# flight_sim_sch.net
KiCad netlist of a schematic drawn in EAGLE
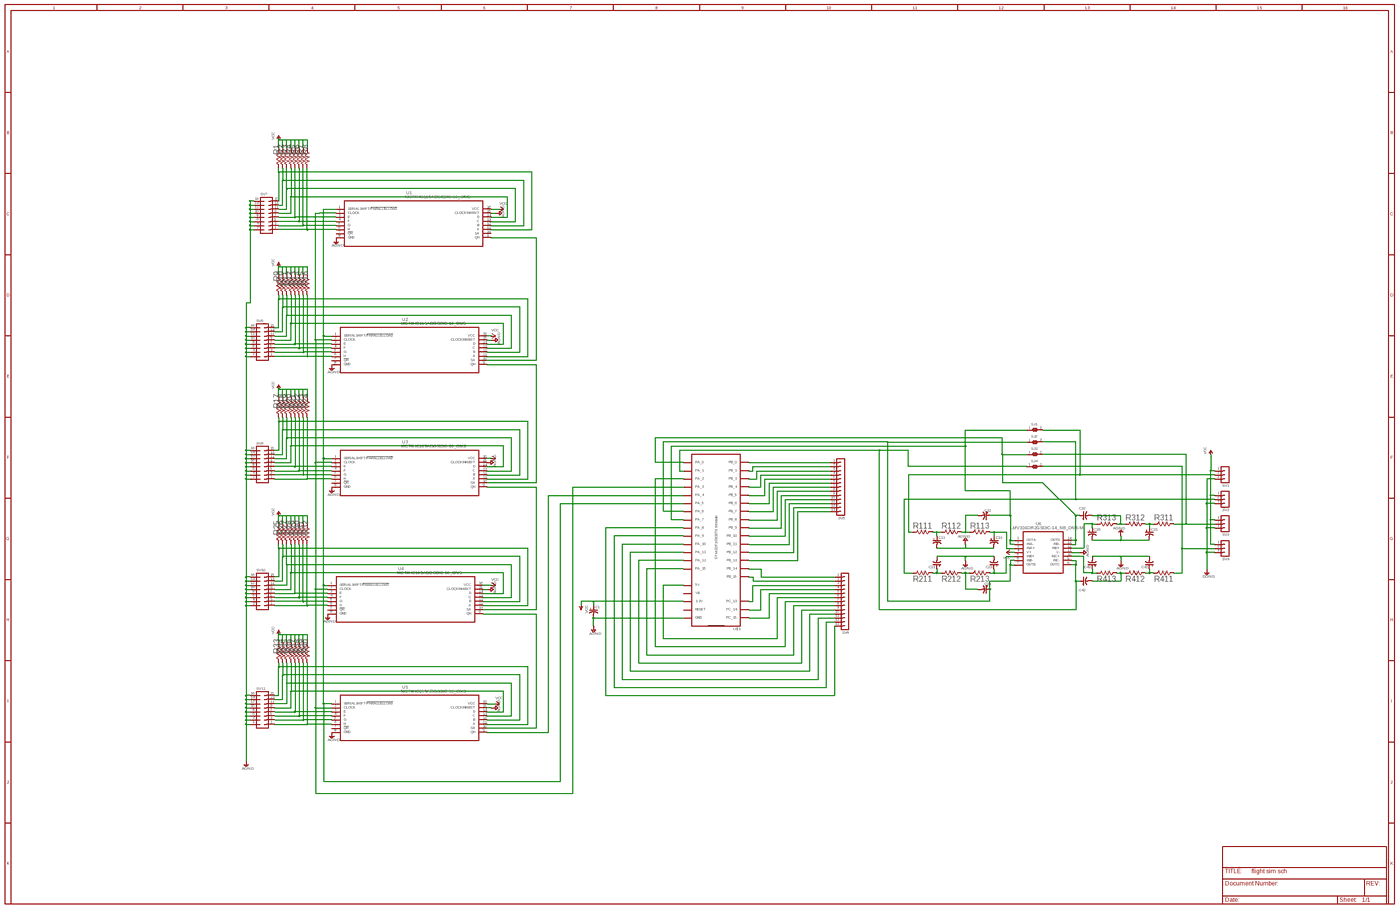
[diagram p0: schematic, sheet 1, overview]
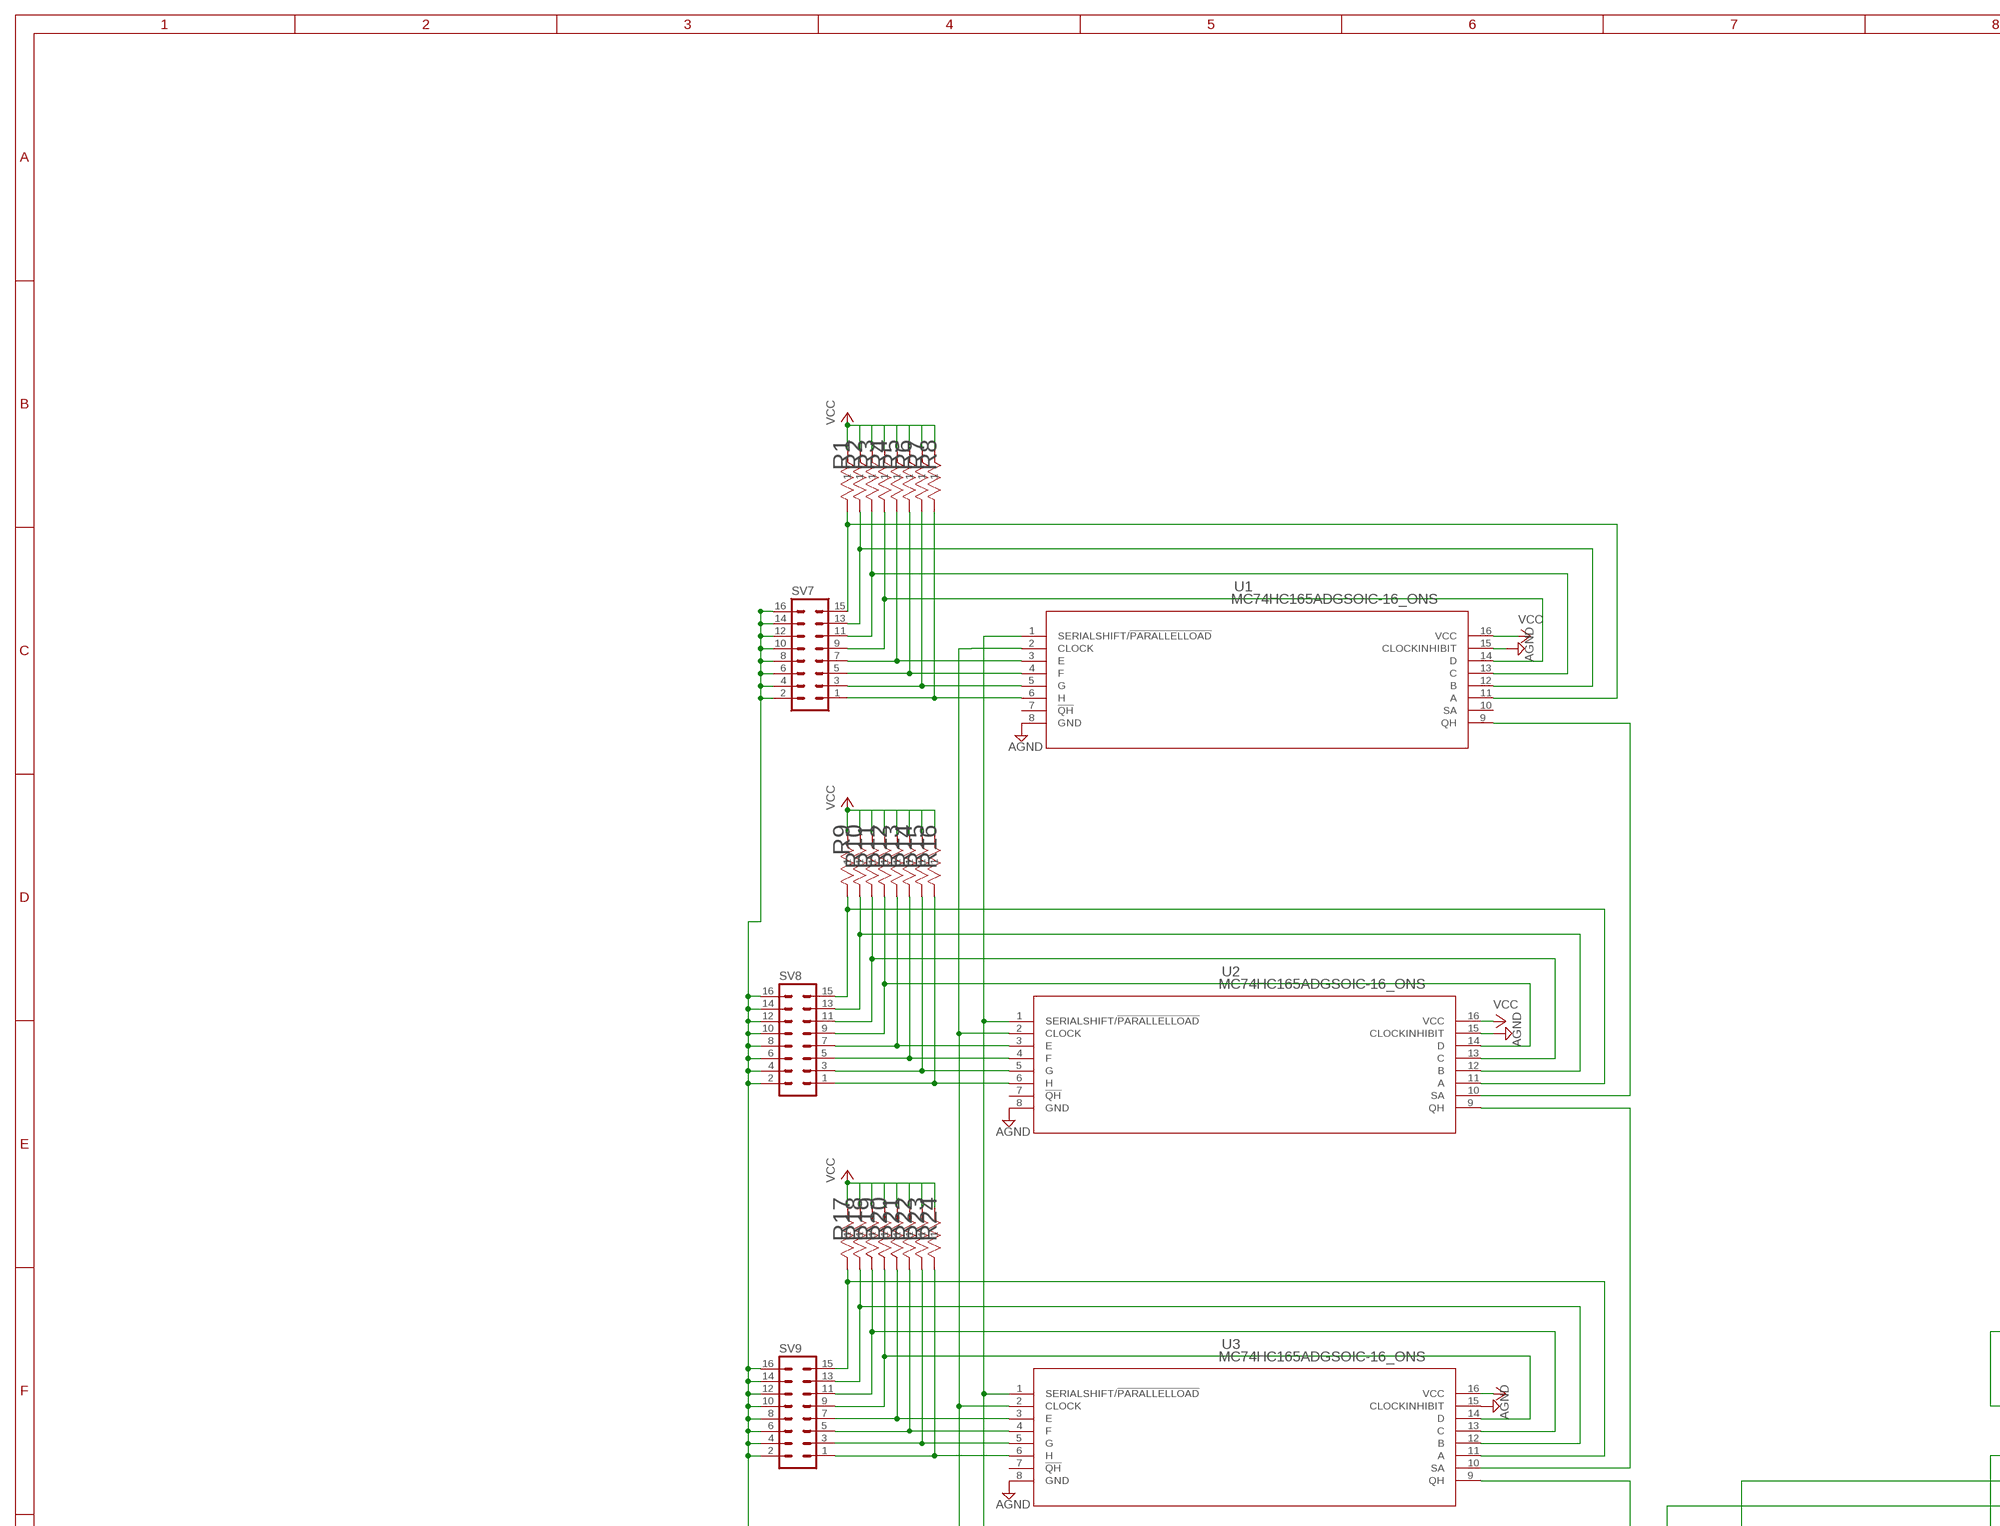
[diagram p1: schematic, sheet 1, part 1 of 4]
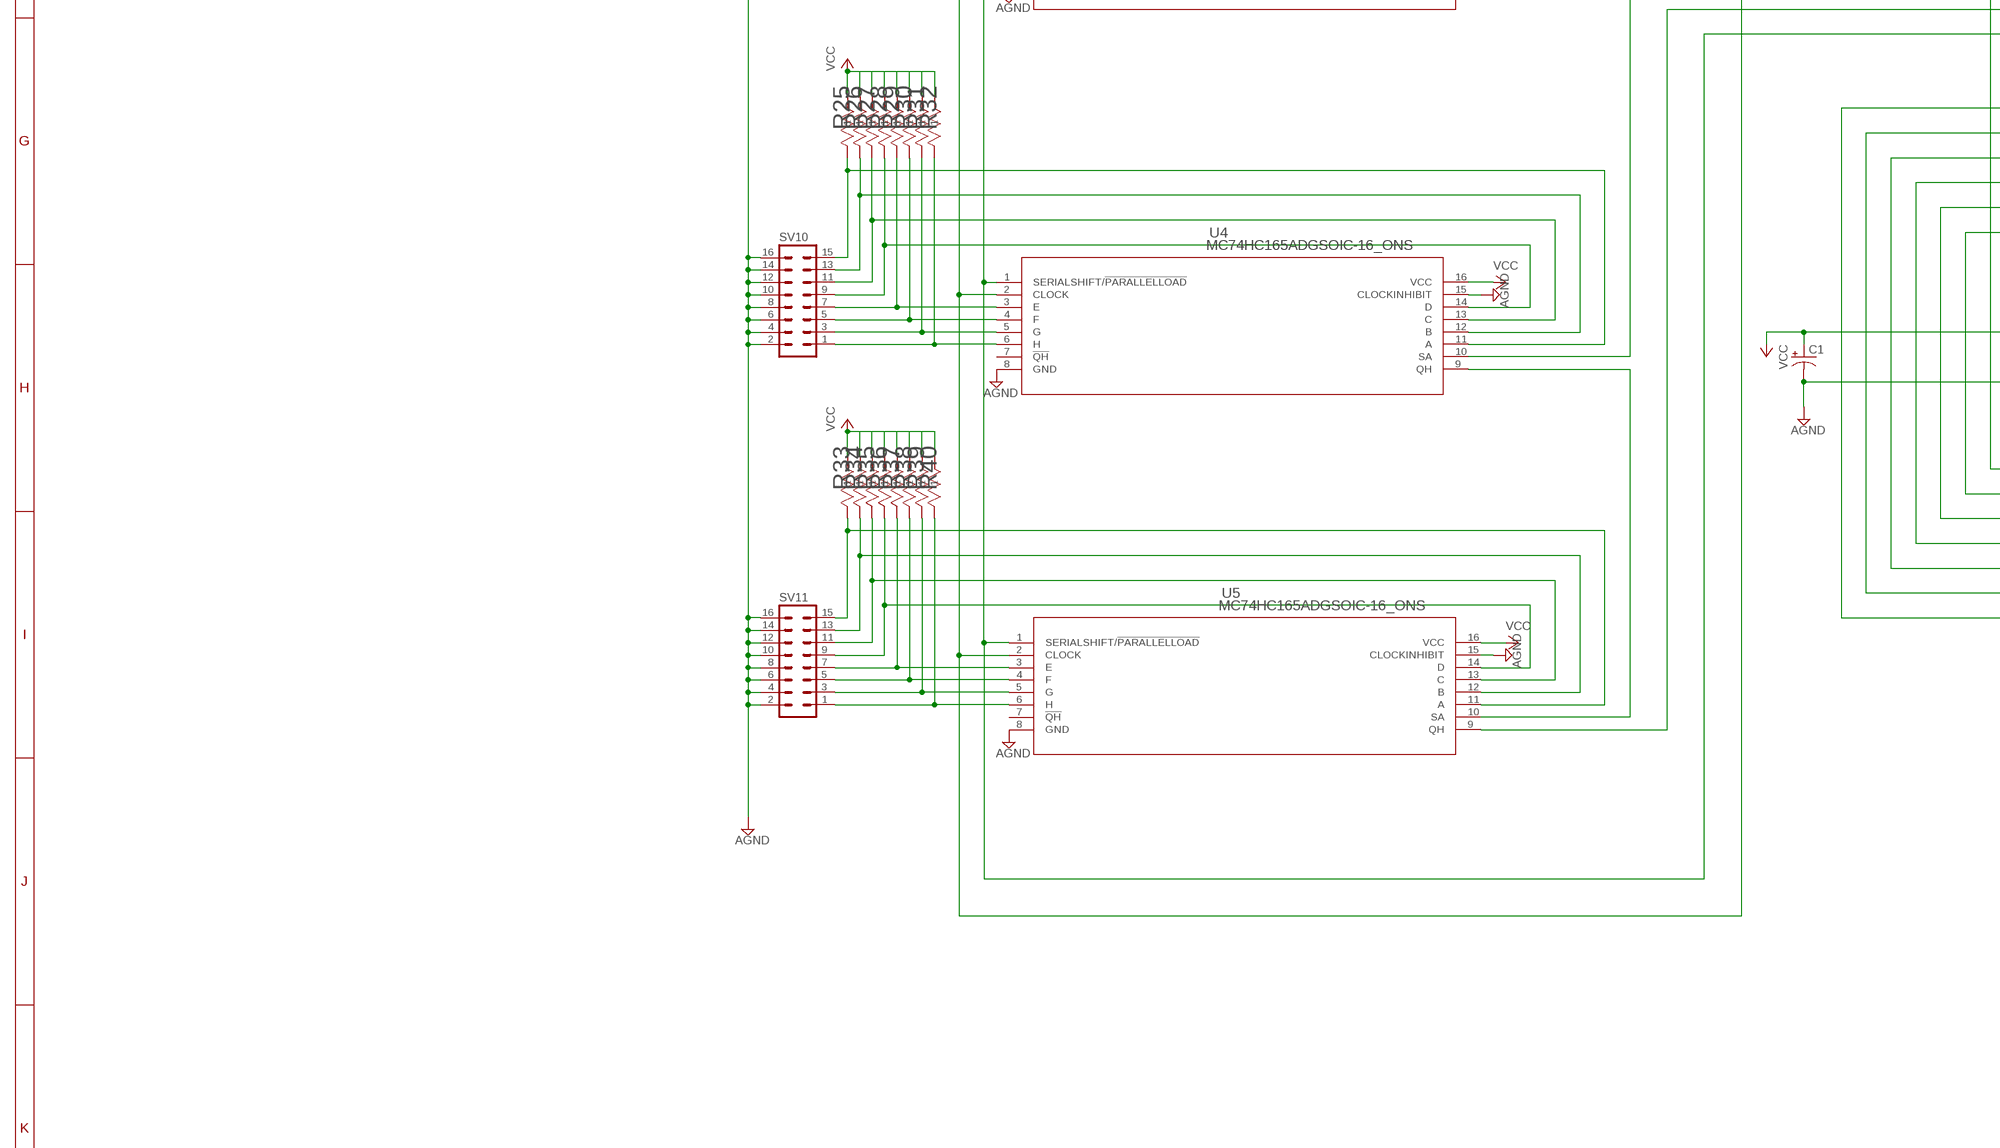
[diagram p2: schematic, sheet 1, part 2 of 4]
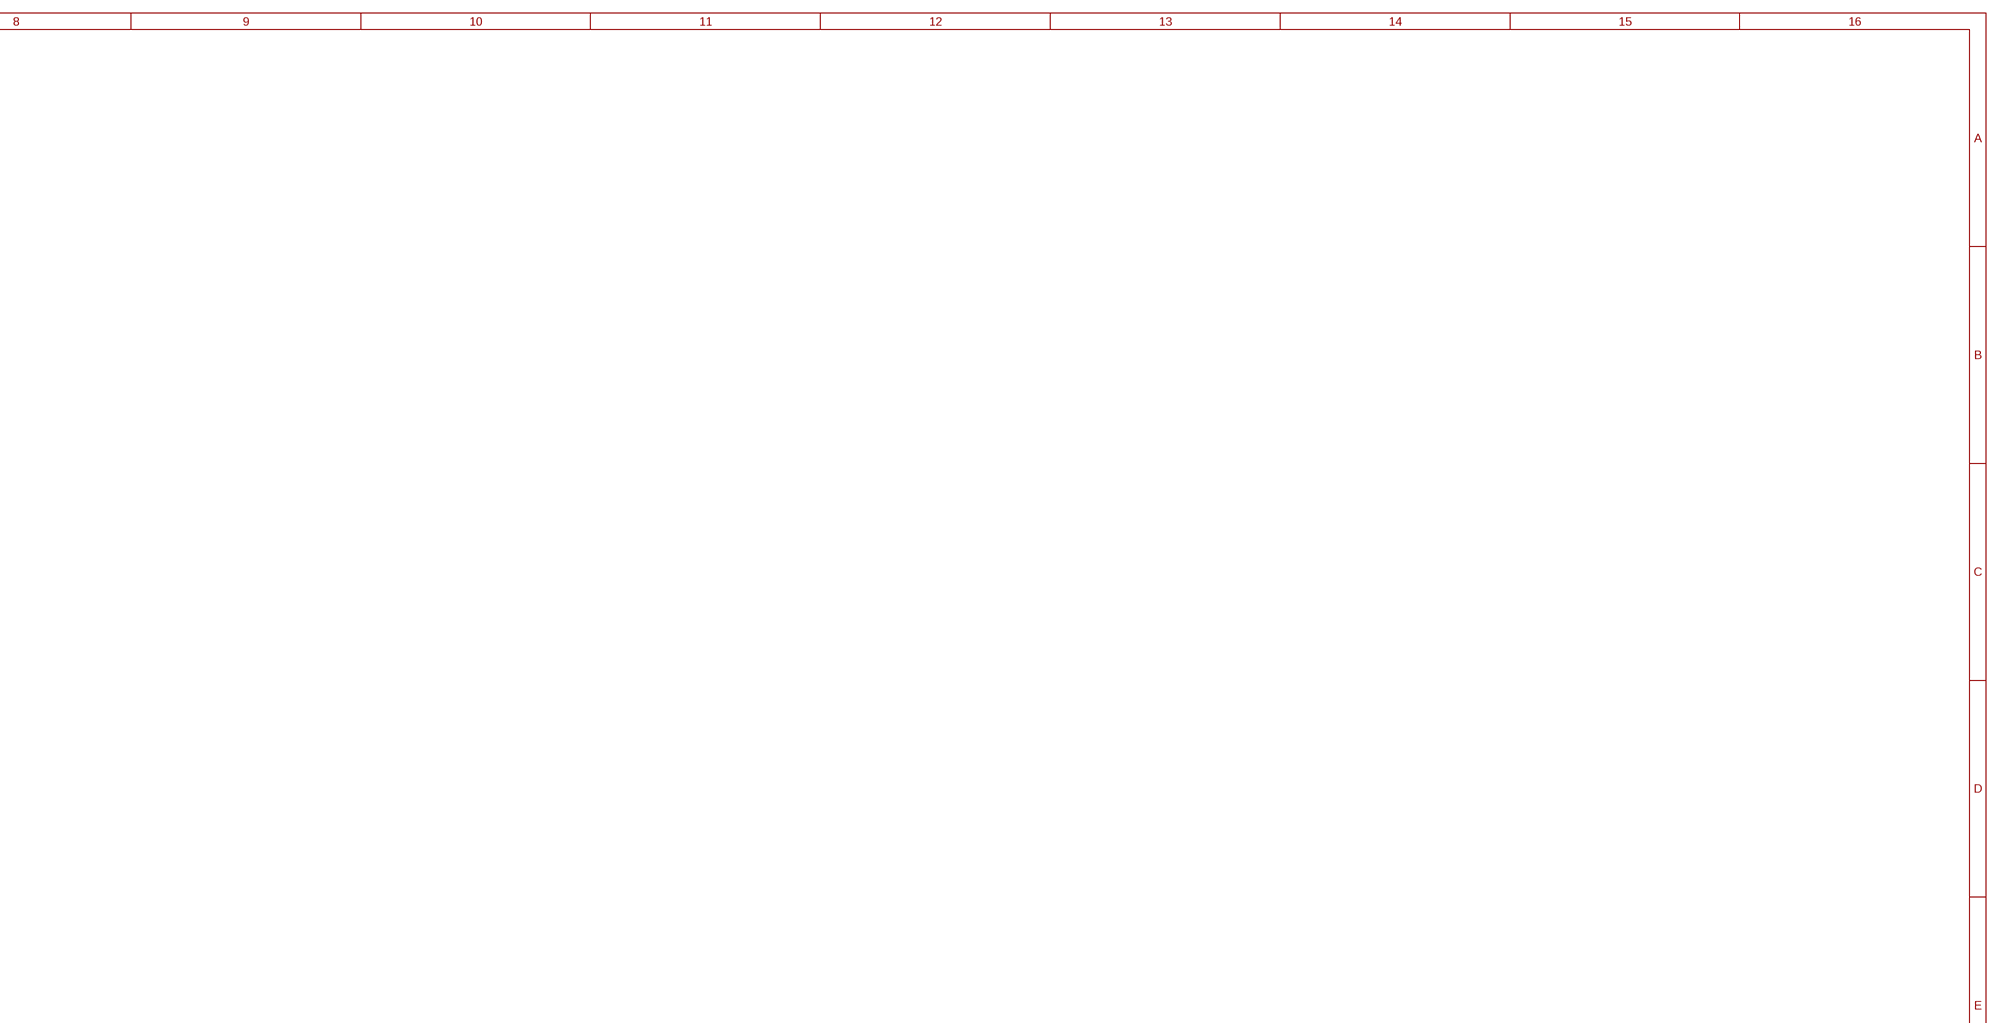
[diagram p3: schematic, sheet 1, part 3 of 4]
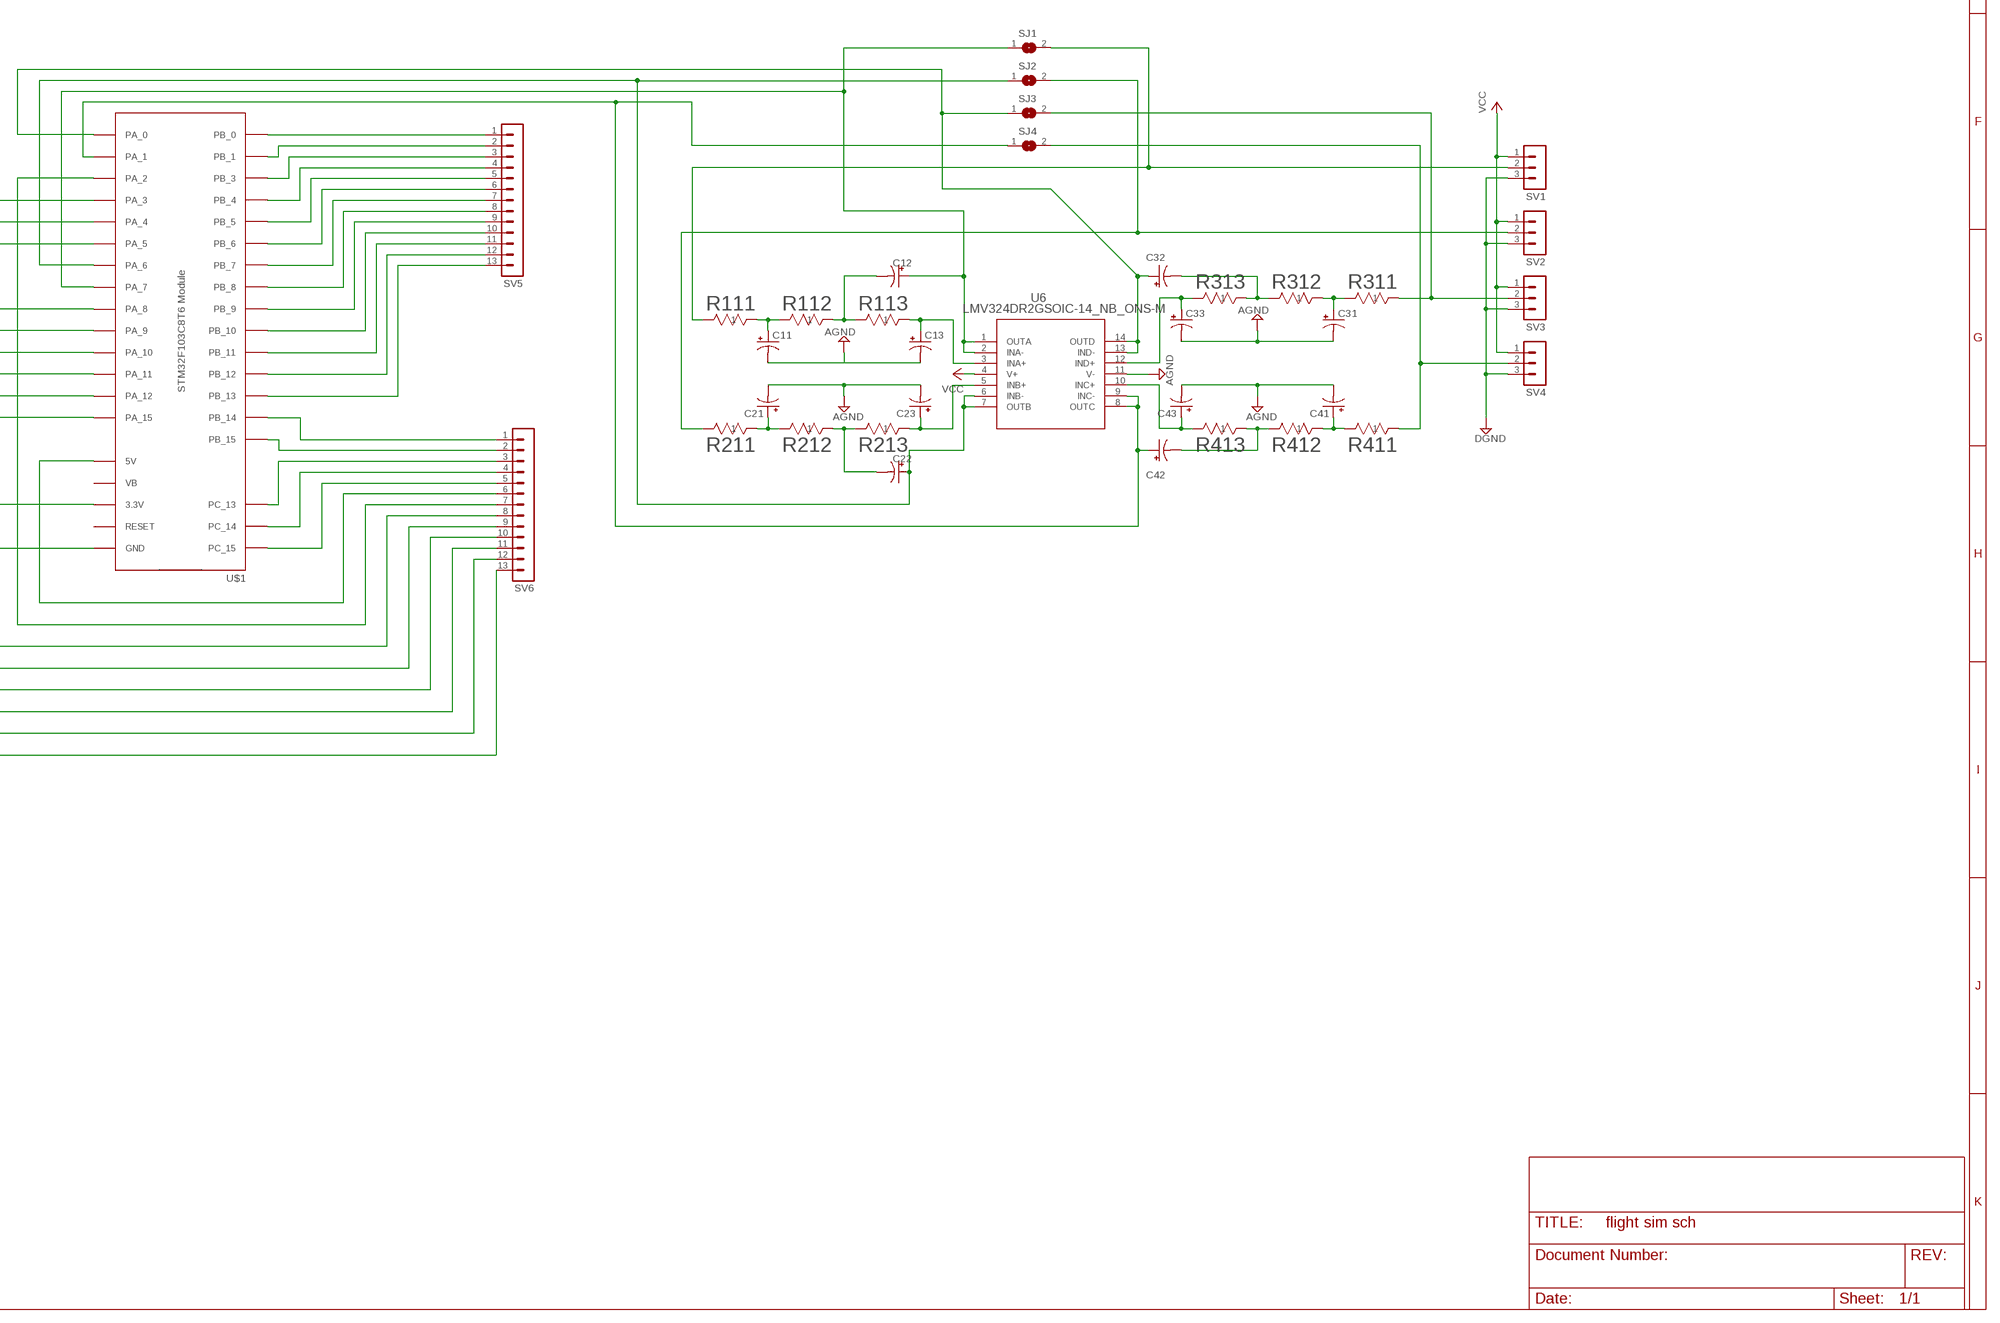
[diagram p4: schematic, sheet 1, part 4 of 4]

(export (version "E")
  (design (tool "Eeschema 10.0.6"))
  (components
    (comp (ref "C1")
      (value "CPOL-USE1.8-4")
      (footprint "eagle-import:E1,8-4")
      (libsource (lib "eagle-import") (part "CPOL-USE1.8-4"))
    )
    (comp (ref "C11")
      (value "CPOL-USE1.8-4")
      (footprint "eagle-import:E1,8-4")
      (libsource (lib "eagle-import") (part "CPOL-USE1.8-4"))
    )
    (comp (ref "C12")
      (value "CPOL-USE1.8-4")
      (footprint "eagle-import:E1,8-4")
      (libsource (lib "eagle-import") (part "CPOL-USE1.8-4"))
    )
    (comp (ref "C13")
      (value "CPOL-USE1.8-4")
      (footprint "eagle-import:E1,8-4")
      (libsource (lib "eagle-import") (part "CPOL-USE1.8-4"))
    )
    (comp (ref "C21")
      (value "CPOL-USE1.8-4")
      (footprint "eagle-import:E1,8-4")
      (libsource (lib "eagle-import") (part "CPOL-USE1.8-4"))
    )
    (comp (ref "C22")
      (value "CPOL-USE1.8-4")
      (footprint "eagle-import:E1,8-4")
      (libsource (lib "eagle-import") (part "CPOL-USE1.8-4"))
    )
    (comp (ref "C23")
      (value "CPOL-USE1.8-4")
      (footprint "eagle-import:E1,8-4")
      (libsource (lib "eagle-import") (part "CPOL-USE1.8-4"))
    )
    (comp (ref "C31")
      (value "CPOL-USE1.8-4")
      (footprint "eagle-import:E1,8-4")
      (libsource (lib "eagle-import") (part "CPOL-USE1.8-4"))
    )
    (comp (ref "C32")
      (value "CPOL-USE1.8-4")
      (footprint "eagle-import:E1,8-4")
      (libsource (lib "eagle-import") (part "CPOL-USE1.8-4"))
    )
    (comp (ref "C33")
      (value "CPOL-USE1.8-4")
      (footprint "eagle-import:E1,8-4")
      (libsource (lib "eagle-import") (part "CPOL-USE1.8-4"))
    )
    (comp (ref "C41")
      (value "CPOL-USE1.8-4")
      (footprint "eagle-import:E1,8-4")
      (libsource (lib "eagle-import") (part "CPOL-USE1.8-4"))
    )
    (comp (ref "C42")
      (value "CPOL-USE1.8-4")
      (footprint "eagle-import:E1,8-4")
      (libsource (lib "eagle-import") (part "CPOL-USE1.8-4"))
    )
    (comp (ref "C43")
      (value "CPOL-USE1.8-4")
      (footprint "eagle-import:E1,8-4")
      (libsource (lib "eagle-import") (part "CPOL-USE1.8-4"))
    )
    (comp (ref "R1")
      (value "MFR-25FRF52-10KYAG_MF25_YAG")
      (footprint "eagle-import:YAG_MF25_YAG")
      (fields
        (field (name "MANUFACTURER_PART_NUMBER") "MFR-25FRF52-10K")
        (field (name "COPYRIGHT") "Copyright (C) 2022 Ultra Librarian. All rights reserved.")
      )
      (libsource (lib "eagle-import") (part "MFR-25FRF52-10KYAG_MF25_YAG"))
    )
    (comp (ref "R2")
      (value "MFR-25FRF52-10KYAG_MF25_YAG")
      (footprint "eagle-import:YAG_MF25_YAG")
      (fields
        (field (name "MANUFACTURER_PART_NUMBER") "MFR-25FRF52-10K")
        (field (name "COPYRIGHT") "Copyright (C) 2022 Ultra Librarian. All rights reserved.")
      )
      (libsource (lib "eagle-import") (part "MFR-25FRF52-10KYAG_MF25_YAG"))
    )
    (comp (ref "R3")
      (value "MFR-25FRF52-10KYAG_MF25_YAG")
      (footprint "eagle-import:YAG_MF25_YAG")
      (fields
        (field (name "MANUFACTURER_PART_NUMBER") "MFR-25FRF52-10K")
        (field (name "COPYRIGHT") "Copyright (C) 2022 Ultra Librarian. All rights reserved.")
      )
      (libsource (lib "eagle-import") (part "MFR-25FRF52-10KYAG_MF25_YAG"))
    )
    (comp (ref "R4")
      (value "MFR-25FRF52-10KYAG_MF25_YAG")
      (footprint "eagle-import:YAG_MF25_YAG")
      (fields
        (field (name "MANUFACTURER_PART_NUMBER") "MFR-25FRF52-10K")
        (field (name "COPYRIGHT") "Copyright (C) 2022 Ultra Librarian. All rights reserved.")
      )
      (libsource (lib "eagle-import") (part "MFR-25FRF52-10KYAG_MF25_YAG"))
    )
    (comp (ref "R5")
      (value "MFR-25FRF52-10KYAG_MF25_YAG")
      (footprint "eagle-import:YAG_MF25_YAG")
      (fields
        (field (name "MANUFACTURER_PART_NUMBER") "MFR-25FRF52-10K")
        (field (name "COPYRIGHT") "Copyright (C) 2022 Ultra Librarian. All rights reserved.")
      )
      (libsource (lib "eagle-import") (part "MFR-25FRF52-10KYAG_MF25_YAG"))
    )
    (comp (ref "R6")
      (value "MFR-25FRF52-10KYAG_MF25_YAG")
      (footprint "eagle-import:YAG_MF25_YAG")
      (fields
        (field (name "MANUFACTURER_PART_NUMBER") "MFR-25FRF52-10K")
        (field (name "COPYRIGHT") "Copyright (C) 2022 Ultra Librarian. All rights reserved.")
      )
      (libsource (lib "eagle-import") (part "MFR-25FRF52-10KYAG_MF25_YAG"))
    )
    (comp (ref "R7")
      (value "MFR-25FRF52-10KYAG_MF25_YAG")
      (footprint "eagle-import:YAG_MF25_YAG")
      (fields
        (field (name "MANUFACTURER_PART_NUMBER") "MFR-25FRF52-10K")
        (field (name "COPYRIGHT") "Copyright (C) 2022 Ultra Librarian. All rights reserved.")
      )
      (libsource (lib "eagle-import") (part "MFR-25FRF52-10KYAG_MF25_YAG"))
    )
    (comp (ref "R8")
      (value "MFR-25FRF52-10KYAG_MF25_YAG")
      (footprint "eagle-import:YAG_MF25_YAG")
      (fields
        (field (name "MANUFACTURER_PART_NUMBER") "MFR-25FRF52-10K")
        (field (name "COPYRIGHT") "Copyright (C) 2022 Ultra Librarian. All rights reserved.")
      )
      (libsource (lib "eagle-import") (part "MFR-25FRF52-10KYAG_MF25_YAG"))
    )
    (comp (ref "R9")
      (value "MFR-25FRF52-10KYAG_MF25_YAG")
      (footprint "eagle-import:YAG_MF25_YAG")
      (fields
        (field (name "MANUFACTURER_PART_NUMBER") "MFR-25FRF52-10K")
        (field (name "COPYRIGHT") "Copyright (C) 2022 Ultra Librarian. All rights reserved.")
      )
      (libsource (lib "eagle-import") (part "MFR-25FRF52-10KYAG_MF25_YAG"))
    )
    (comp (ref "R10")
      (value "MFR-25FRF52-10KYAG_MF25_YAG")
      (footprint "eagle-import:YAG_MF25_YAG")
      (fields
        (field (name "MANUFACTURER_PART_NUMBER") "MFR-25FRF52-10K")
        (field (name "COPYRIGHT") "Copyright (C) 2022 Ultra Librarian. All rights reserved.")
      )
      (libsource (lib "eagle-import") (part "MFR-25FRF52-10KYAG_MF25_YAG"))
    )
    (comp (ref "R11")
      (value "MFR-25FRF52-10KYAG_MF25_YAG")
      (footprint "eagle-import:YAG_MF25_YAG")
      (fields
        (field (name "MANUFACTURER_PART_NUMBER") "MFR-25FRF52-10K")
        (field (name "COPYRIGHT") "Copyright (C) 2022 Ultra Librarian. All rights reserved.")
      )
      (libsource (lib "eagle-import") (part "MFR-25FRF52-10KYAG_MF25_YAG"))
    )
    (comp (ref "R12")
      (value "MFR-25FRF52-10KYAG_MF25_YAG")
      (footprint "eagle-import:YAG_MF25_YAG")
      (fields
        (field (name "MANUFACTURER_PART_NUMBER") "MFR-25FRF52-10K")
        (field (name "COPYRIGHT") "Copyright (C) 2022 Ultra Librarian. All rights reserved.")
      )
      (libsource (lib "eagle-import") (part "MFR-25FRF52-10KYAG_MF25_YAG"))
    )
    (comp (ref "R13")
      (value "MFR-25FRF52-10KYAG_MF25_YAG")
      (footprint "eagle-import:YAG_MF25_YAG")
      (fields
        (field (name "MANUFACTURER_PART_NUMBER") "MFR-25FRF52-10K")
        (field (name "COPYRIGHT") "Copyright (C) 2022 Ultra Librarian. All rights reserved.")
      )
      (libsource (lib "eagle-import") (part "MFR-25FRF52-10KYAG_MF25_YAG"))
    )
    (comp (ref "R14")
      (value "MFR-25FRF52-10KYAG_MF25_YAG")
      (footprint "eagle-import:YAG_MF25_YAG")
      (fields
        (field (name "MANUFACTURER_PART_NUMBER") "MFR-25FRF52-10K")
        (field (name "COPYRIGHT") "Copyright (C) 2022 Ultra Librarian. All rights reserved.")
      )
      (libsource (lib "eagle-import") (part "MFR-25FRF52-10KYAG_MF25_YAG"))
    )
    (comp (ref "R15")
      (value "MFR-25FRF52-10KYAG_MF25_YAG")
      (footprint "eagle-import:YAG_MF25_YAG")
      (fields
        (field (name "MANUFACTURER_PART_NUMBER") "MFR-25FRF52-10K")
        (field (name "COPYRIGHT") "Copyright (C) 2022 Ultra Librarian. All rights reserved.")
      )
      (libsource (lib "eagle-import") (part "MFR-25FRF52-10KYAG_MF25_YAG"))
    )
    (comp (ref "R16")
      (value "MFR-25FRF52-10KYAG_MF25_YAG")
      (footprint "eagle-import:YAG_MF25_YAG")
      (fields
        (field (name "MANUFACTURER_PART_NUMBER") "MFR-25FRF52-10K")
        (field (name "COPYRIGHT") "Copyright (C) 2022 Ultra Librarian. All rights reserved.")
      )
      (libsource (lib "eagle-import") (part "MFR-25FRF52-10KYAG_MF25_YAG"))
    )
    (comp (ref "R17")
      (value "MFR-25FRF52-10KYAG_MF25_YAG")
      (footprint "eagle-import:YAG_MF25_YAG")
      (fields
        (field (name "MANUFACTURER_PART_NUMBER") "MFR-25FRF52-10K")
        (field (name "COPYRIGHT") "Copyright (C) 2022 Ultra Librarian. All rights reserved.")
      )
      (libsource (lib "eagle-import") (part "MFR-25FRF52-10KYAG_MF25_YAG"))
    )
    (comp (ref "R18")
      (value "MFR-25FRF52-10KYAG_MF25_YAG")
      (footprint "eagle-import:YAG_MF25_YAG")
      (fields
        (field (name "MANUFACTURER_PART_NUMBER") "MFR-25FRF52-10K")
        (field (name "COPYRIGHT") "Copyright (C) 2022 Ultra Librarian. All rights reserved.")
      )
      (libsource (lib "eagle-import") (part "MFR-25FRF52-10KYAG_MF25_YAG"))
    )
    (comp (ref "R19")
      (value "MFR-25FRF52-10KYAG_MF25_YAG")
      (footprint "eagle-import:YAG_MF25_YAG")
      (fields
        (field (name "MANUFACTURER_PART_NUMBER") "MFR-25FRF52-10K")
        (field (name "COPYRIGHT") "Copyright (C) 2022 Ultra Librarian. All rights reserved.")
      )
      (libsource (lib "eagle-import") (part "MFR-25FRF52-10KYAG_MF25_YAG"))
    )
    (comp (ref "R20")
      (value "MFR-25FRF52-10KYAG_MF25_YAG")
      (footprint "eagle-import:YAG_MF25_YAG")
      (fields
        (field (name "MANUFACTURER_PART_NUMBER") "MFR-25FRF52-10K")
        (field (name "COPYRIGHT") "Copyright (C) 2022 Ultra Librarian. All rights reserved.")
      )
      (libsource (lib "eagle-import") (part "MFR-25FRF52-10KYAG_MF25_YAG"))
    )
    (comp (ref "R21")
      (value "MFR-25FRF52-10KYAG_MF25_YAG")
      (footprint "eagle-import:YAG_MF25_YAG")
      (fields
        (field (name "MANUFACTURER_PART_NUMBER") "MFR-25FRF52-10K")
        (field (name "COPYRIGHT") "Copyright (C) 2022 Ultra Librarian. All rights reserved.")
      )
      (libsource (lib "eagle-import") (part "MFR-25FRF52-10KYAG_MF25_YAG"))
    )
    (comp (ref "R22")
      (value "MFR-25FRF52-10KYAG_MF25_YAG")
      (footprint "eagle-import:YAG_MF25_YAG")
      (fields
        (field (name "MANUFACTURER_PART_NUMBER") "MFR-25FRF52-10K")
        (field (name "COPYRIGHT") "Copyright (C) 2022 Ultra Librarian. All rights reserved.")
      )
      (libsource (lib "eagle-import") (part "MFR-25FRF52-10KYAG_MF25_YAG"))
    )
    (comp (ref "R23")
      (value "MFR-25FRF52-10KYAG_MF25_YAG")
      (footprint "eagle-import:YAG_MF25_YAG")
      (fields
        (field (name "MANUFACTURER_PART_NUMBER") "MFR-25FRF52-10K")
        (field (name "COPYRIGHT") "Copyright (C) 2022 Ultra Librarian. All rights reserved.")
      )
      (libsource (lib "eagle-import") (part "MFR-25FRF52-10KYAG_MF25_YAG"))
    )
    (comp (ref "R24")
      (value "MFR-25FRF52-10KYAG_MF25_YAG")
      (footprint "eagle-import:YAG_MF25_YAG")
      (fields
        (field (name "MANUFACTURER_PART_NUMBER") "MFR-25FRF52-10K")
        (field (name "COPYRIGHT") "Copyright (C) 2022 Ultra Librarian. All rights reserved.")
      )
      (libsource (lib "eagle-import") (part "MFR-25FRF52-10KYAG_MF25_YAG"))
    )
    (comp (ref "R25")
      (value "MFR-25FRF52-10KYAG_MF25_YAG")
      (footprint "eagle-import:YAG_MF25_YAG")
      (fields
        (field (name "MANUFACTURER_PART_NUMBER") "MFR-25FRF52-10K")
        (field (name "COPYRIGHT") "Copyright (C) 2022 Ultra Librarian. All rights reserved.")
      )
      (libsource (lib "eagle-import") (part "MFR-25FRF52-10KYAG_MF25_YAG"))
    )
    (comp (ref "R26")
      (value "MFR-25FRF52-10KYAG_MF25_YAG")
      (footprint "eagle-import:YAG_MF25_YAG")
      (fields
        (field (name "MANUFACTURER_PART_NUMBER") "MFR-25FRF52-10K")
        (field (name "COPYRIGHT") "Copyright (C) 2022 Ultra Librarian. All rights reserved.")
      )
      (libsource (lib "eagle-import") (part "MFR-25FRF52-10KYAG_MF25_YAG"))
    )
    (comp (ref "R27")
      (value "MFR-25FRF52-10KYAG_MF25_YAG")
      (footprint "eagle-import:YAG_MF25_YAG")
      (fields
        (field (name "MANUFACTURER_PART_NUMBER") "MFR-25FRF52-10K")
        (field (name "COPYRIGHT") "Copyright (C) 2022 Ultra Librarian. All rights reserved.")
      )
      (libsource (lib "eagle-import") (part "MFR-25FRF52-10KYAG_MF25_YAG"))
    )
    (comp (ref "R28")
      (value "MFR-25FRF52-10KYAG_MF25_YAG")
      (footprint "eagle-import:YAG_MF25_YAG")
      (fields
        (field (name "MANUFACTURER_PART_NUMBER") "MFR-25FRF52-10K")
        (field (name "COPYRIGHT") "Copyright (C) 2022 Ultra Librarian. All rights reserved.")
      )
      (libsource (lib "eagle-import") (part "MFR-25FRF52-10KYAG_MF25_YAG"))
    )
    (comp (ref "R29")
      (value "MFR-25FRF52-10KYAG_MF25_YAG")
      (footprint "eagle-import:YAG_MF25_YAG")
      (fields
        (field (name "MANUFACTURER_PART_NUMBER") "MFR-25FRF52-10K")
        (field (name "COPYRIGHT") "Copyright (C) 2022 Ultra Librarian. All rights reserved.")
      )
      (libsource (lib "eagle-import") (part "MFR-25FRF52-10KYAG_MF25_YAG"))
    )
    (comp (ref "R30")
      (value "MFR-25FRF52-10KYAG_MF25_YAG")
      (footprint "eagle-import:YAG_MF25_YAG")
      (fields
        (field (name "MANUFACTURER_PART_NUMBER") "MFR-25FRF52-10K")
        (field (name "COPYRIGHT") "Copyright (C) 2022 Ultra Librarian. All rights reserved.")
      )
      (libsource (lib "eagle-import") (part "MFR-25FRF52-10KYAG_MF25_YAG"))
    )
    (comp (ref "R31")
      (value "MFR-25FRF52-10KYAG_MF25_YAG")
      (footprint "eagle-import:YAG_MF25_YAG")
      (fields
        (field (name "MANUFACTURER_PART_NUMBER") "MFR-25FRF52-10K")
        (field (name "COPYRIGHT") "Copyright (C) 2022 Ultra Librarian. All rights reserved.")
      )
      (libsource (lib "eagle-import") (part "MFR-25FRF52-10KYAG_MF25_YAG"))
    )
    (comp (ref "R32")
      (value "MFR-25FRF52-10KYAG_MF25_YAG")
      (footprint "eagle-import:YAG_MF25_YAG")
      (fields
        (field (name "MANUFACTURER_PART_NUMBER") "MFR-25FRF52-10K")
        (field (name "COPYRIGHT") "Copyright (C) 2022 Ultra Librarian. All rights reserved.")
      )
      (libsource (lib "eagle-import") (part "MFR-25FRF52-10KYAG_MF25_YAG"))
    )
    (comp (ref "R33")
      (value "MFR-25FRF52-10KYAG_MF25_YAG")
      (footprint "eagle-import:YAG_MF25_YAG")
      (fields
        (field (name "MANUFACTURER_PART_NUMBER") "MFR-25FRF52-10K")
        (field (name "COPYRIGHT") "Copyright (C) 2022 Ultra Librarian. All rights reserved.")
      )
      (libsource (lib "eagle-import") (part "MFR-25FRF52-10KYAG_MF25_YAG"))
    )
    (comp (ref "R34")
      (value "MFR-25FRF52-10KYAG_MF25_YAG")
      (footprint "eagle-import:YAG_MF25_YAG")
      (fields
        (field (name "MANUFACTURER_PART_NUMBER") "MFR-25FRF52-10K")
        (field (name "COPYRIGHT") "Copyright (C) 2022 Ultra Librarian. All rights reserved.")
      )
      (libsource (lib "eagle-import") (part "MFR-25FRF52-10KYAG_MF25_YAG"))
    )
    (comp (ref "R35")
      (value "MFR-25FRF52-10KYAG_MF25_YAG")
      (footprint "eagle-import:YAG_MF25_YAG")
      (fields
        (field (name "MANUFACTURER_PART_NUMBER") "MFR-25FRF52-10K")
        (field (name "COPYRIGHT") "Copyright (C) 2022 Ultra Librarian. All rights reserved.")
      )
      (libsource (lib "eagle-import") (part "MFR-25FRF52-10KYAG_MF25_YAG"))
    )
    (comp (ref "R36")
      (value "MFR-25FRF52-10KYAG_MF25_YAG")
      (footprint "eagle-import:YAG_MF25_YAG")
      (fields
        (field (name "MANUFACTURER_PART_NUMBER") "MFR-25FRF52-10K")
        (field (name "COPYRIGHT") "Copyright (C) 2022 Ultra Librarian. All rights reserved.")
      )
      (libsource (lib "eagle-import") (part "MFR-25FRF52-10KYAG_MF25_YAG"))
    )
    (comp (ref "R37")
      (value "MFR-25FRF52-10KYAG_MF25_YAG")
      (footprint "eagle-import:YAG_MF25_YAG")
      (fields
        (field (name "MANUFACTURER_PART_NUMBER") "MFR-25FRF52-10K")
        (field (name "COPYRIGHT") "Copyright (C) 2022 Ultra Librarian. All rights reserved.")
      )
      (libsource (lib "eagle-import") (part "MFR-25FRF52-10KYAG_MF25_YAG"))
    )
    (comp (ref "R38")
      (value "MFR-25FRF52-10KYAG_MF25_YAG")
      (footprint "eagle-import:YAG_MF25_YAG")
      (fields
        (field (name "MANUFACTURER_PART_NUMBER") "MFR-25FRF52-10K")
        (field (name "COPYRIGHT") "Copyright (C) 2022 Ultra Librarian. All rights reserved.")
      )
      (libsource (lib "eagle-import") (part "MFR-25FRF52-10KYAG_MF25_YAG"))
    )
    (comp (ref "R39")
      (value "MFR-25FRF52-10KYAG_MF25_YAG")
      (footprint "eagle-import:YAG_MF25_YAG")
      (fields
        (field (name "MANUFACTURER_PART_NUMBER") "MFR-25FRF52-10K")
        (field (name "COPYRIGHT") "Copyright (C) 2022 Ultra Librarian. All rights reserved.")
      )
      (libsource (lib "eagle-import") (part "MFR-25FRF52-10KYAG_MF25_YAG"))
    )
    (comp (ref "R40")
      (value "MFR-25FRF52-10KYAG_MF25_YAG")
      (footprint "eagle-import:YAG_MF25_YAG")
      (fields
        (field (name "MANUFACTURER_PART_NUMBER") "MFR-25FRF52-10K")
        (field (name "COPYRIGHT") "Copyright (C) 2022 Ultra Librarian. All rights reserved.")
      )
      (libsource (lib "eagle-import") (part "MFR-25FRF52-10KYAG_MF25_YAG"))
    )
    (comp (ref "R111")
      (value "MFR-25FRF52-10KYAG_MF25_YAG")
      (footprint "eagle-import:YAG_MF25_YAG")
      (fields
        (field (name "MANUFACTURER_PART_NUMBER") "MFR-25FRF52-10K")
        (field (name "COPYRIGHT") "Copyright (C) 2022 Ultra Librarian. All rights reserved.")
      )
      (libsource (lib "eagle-import") (part "MFR-25FRF52-10KYAG_MF25_YAG"))
    )
    (comp (ref "R112")
      (value "MFR-25FRF52-10KYAG_MF25_YAG")
      (footprint "eagle-import:YAG_MF25_YAG")
      (fields
        (field (name "MANUFACTURER_PART_NUMBER") "MFR-25FRF52-10K")
        (field (name "COPYRIGHT") "Copyright (C) 2022 Ultra Librarian. All rights reserved.")
      )
      (libsource (lib "eagle-import") (part "MFR-25FRF52-10KYAG_MF25_YAG"))
    )
    (comp (ref "R113")
      (value "MFR-25FRF52-10KYAG_MF25_YAG")
      (footprint "eagle-import:YAG_MF25_YAG")
      (fields
        (field (name "MANUFACTURER_PART_NUMBER") "MFR-25FRF52-10K")
        (field (name "COPYRIGHT") "Copyright (C) 2022 Ultra Librarian. All rights reserved.")
      )
      (libsource (lib "eagle-import") (part "MFR-25FRF52-10KYAG_MF25_YAG"))
    )
    (comp (ref "R211")
      (value "MFR-25FRF52-10KYAG_MF25_YAG")
      (footprint "eagle-import:YAG_MF25_YAG")
      (fields
        (field (name "MANUFACTURER_PART_NUMBER") "MFR-25FRF52-10K")
        (field (name "COPYRIGHT") "Copyright (C) 2022 Ultra Librarian. All rights reserved.")
      )
      (libsource (lib "eagle-import") (part "MFR-25FRF52-10KYAG_MF25_YAG"))
    )
    (comp (ref "R212")
      (value "MFR-25FRF52-10KYAG_MF25_YAG")
      (footprint "eagle-import:YAG_MF25_YAG")
      (fields
        (field (name "MANUFACTURER_PART_NUMBER") "MFR-25FRF52-10K")
        (field (name "COPYRIGHT") "Copyright (C) 2022 Ultra Librarian. All rights reserved.")
      )
      (libsource (lib "eagle-import") (part "MFR-25FRF52-10KYAG_MF25_YAG"))
    )
    (comp (ref "R213")
      (value "MFR-25FRF52-10KYAG_MF25_YAG")
      (footprint "eagle-import:YAG_MF25_YAG")
      (fields
        (field (name "MANUFACTURER_PART_NUMBER") "MFR-25FRF52-10K")
        (field (name "COPYRIGHT") "Copyright (C) 2022 Ultra Librarian. All rights reserved.")
      )
      (libsource (lib "eagle-import") (part "MFR-25FRF52-10KYAG_MF25_YAG"))
    )
    (comp (ref "R311")
      (value "MFR-25FRF52-10KYAG_MF25_YAG")
      (footprint "eagle-import:YAG_MF25_YAG")
      (fields
        (field (name "MANUFACTURER_PART_NUMBER") "MFR-25FRF52-10K")
        (field (name "COPYRIGHT") "Copyright (C) 2022 Ultra Librarian. All rights reserved.")
      )
      (libsource (lib "eagle-import") (part "MFR-25FRF52-10KYAG_MF25_YAG"))
    )
    (comp (ref "R312")
      (value "MFR-25FRF52-10KYAG_MF25_YAG")
      (footprint "eagle-import:YAG_MF25_YAG")
      (fields
        (field (name "MANUFACTURER_PART_NUMBER") "MFR-25FRF52-10K")
        (field (name "COPYRIGHT") "Copyright (C) 2022 Ultra Librarian. All rights reserved.")
      )
      (libsource (lib "eagle-import") (part "MFR-25FRF52-10KYAG_MF25_YAG"))
    )
    (comp (ref "R313")
      (value "MFR-25FRF52-10KYAG_MF25_YAG")
      (footprint "eagle-import:YAG_MF25_YAG")
      (fields
        (field (name "MANUFACTURER_PART_NUMBER") "MFR-25FRF52-10K")
        (field (name "COPYRIGHT") "Copyright (C) 2022 Ultra Librarian. All rights reserved.")
      )
      (libsource (lib "eagle-import") (part "MFR-25FRF52-10KYAG_MF25_YAG"))
    )
    (comp (ref "R411")
      (value "MFR-25FRF52-10KYAG_MF25_YAG")
      (footprint "eagle-import:YAG_MF25_YAG")
      (fields
        (field (name "MANUFACTURER_PART_NUMBER") "MFR-25FRF52-10K")
        (field (name "COPYRIGHT") "Copyright (C) 2022 Ultra Librarian. All rights reserved.")
      )
      (libsource (lib "eagle-import") (part "MFR-25FRF52-10KYAG_MF25_YAG"))
    )
    (comp (ref "R412")
      (value "MFR-25FRF52-10KYAG_MF25_YAG")
      (footprint "eagle-import:YAG_MF25_YAG")
      (fields
        (field (name "MANUFACTURER_PART_NUMBER") "MFR-25FRF52-10K")
        (field (name "COPYRIGHT") "Copyright (C) 2022 Ultra Librarian. All rights reserved.")
      )
      (libsource (lib "eagle-import") (part "MFR-25FRF52-10KYAG_MF25_YAG"))
    )
    (comp (ref "R413")
      (value "MFR-25FRF52-10KYAG_MF25_YAG")
      (footprint "eagle-import:YAG_MF25_YAG")
      (fields
        (field (name "MANUFACTURER_PART_NUMBER") "MFR-25FRF52-10K")
        (field (name "COPYRIGHT") "Copyright (C) 2022 Ultra Librarian. All rights reserved.")
      )
      (libsource (lib "eagle-import") (part "MFR-25FRF52-10KYAG_MF25_YAG"))
    )
    (comp (ref "SJ1") (value "SJ") (footprint "eagle-import:SJ") (libsource (lib "eagle-import") (part "SJ")))
    (comp (ref "SJ2") (value "SJ") (footprint "eagle-import:SJ") (libsource (lib "eagle-import") (part "SJ")))
    (comp (ref "SJ3") (value "SJ") (footprint "eagle-import:SJ") (libsource (lib "eagle-import") (part "SJ")))
    (comp (ref "SJ4") (value "SJ") (footprint "eagle-import:SJ") (libsource (lib "eagle-import") (part "SJ")))
    (comp (ref "SV1")
      (value "MA03-1")
      (footprint "eagle-import:MA03-1")
      (libsource (lib "eagle-import") (part "MA03-1"))
    )
    (comp (ref "SV2")
      (value "MA03-1")
      (footprint "eagle-import:MA03-1")
      (libsource (lib "eagle-import") (part "MA03-1"))
    )
    (comp (ref "SV3")
      (value "MA03-1")
      (footprint "eagle-import:MA03-1")
      (libsource (lib "eagle-import") (part "MA03-1"))
    )
    (comp (ref "SV4")
      (value "MA03-1")
      (footprint "eagle-import:MA03-1")
      (libsource (lib "eagle-import") (part "MA03-1"))
    )
    (comp (ref "SV5")
      (value "MA13-1")
      (footprint "eagle-import:MA13-1")
      (libsource (lib "eagle-import") (part "MA13-1"))
    )
    (comp (ref "SV6")
      (value "MA13-1")
      (footprint "eagle-import:MA13-1")
      (libsource (lib "eagle-import") (part "MA13-1"))
    )
    (comp (ref "SV7")
      (value "MA08-2")
      (footprint "eagle-import:MA08-2")
      (libsource (lib "eagle-import") (part "MA08-2"))
    )
    (comp (ref "SV8")
      (value "MA08-2")
      (footprint "eagle-import:MA08-2")
      (libsource (lib "eagle-import") (part "MA08-2"))
    )
    (comp (ref "SV9")
      (value "MA08-2")
      (footprint "eagle-import:MA08-2")
      (libsource (lib "eagle-import") (part "MA08-2"))
    )
    (comp (ref "SV10")
      (value "MA08-2")
      (footprint "eagle-import:MA08-2")
      (libsource (lib "eagle-import") (part "MA08-2"))
    )
    (comp (ref "SV11")
      (value "MA08-2")
      (footprint "eagle-import:MA08-2")
      (libsource (lib "eagle-import") (part "MA08-2"))
    )
    (comp (ref "U$1")
      (value "STM32F103C8T6-MODULE")
      (footprint "eagle-import:STM32F103C8T6-MODULE")
      (libsource (lib "eagle-import") (part "STM32F103C8T6-MODULE"))
    )
    (comp (ref "U1")
      (value "MC74HC165ADGSOIC-16_ONS")
      (footprint "eagle-import:SOIC-16_ONS")
      (fields
        (field (name "MANUFACTURER_PART_NUMBER") "MC74HC165ADG")
        (field (name "COPYRIGHT") "Copyright (C) 2022 Ultra Librarian. All rights reserved.")
      )
      (libsource (lib "eagle-import") (part "MC74HC165ADGSOIC-16_ONS"))
    )
    (comp (ref "U2")
      (value "MC74HC165ADGSOIC-16_ONS")
      (footprint "eagle-import:SOIC-16_ONS")
      (fields
        (field (name "MANUFACTURER_PART_NUMBER") "MC74HC165ADG")
        (field (name "COPYRIGHT") "Copyright (C) 2022 Ultra Librarian. All rights reserved.")
      )
      (libsource (lib "eagle-import") (part "MC74HC165ADGSOIC-16_ONS"))
    )
    (comp (ref "U3")
      (value "MC74HC165ADGSOIC-16_ONS")
      (footprint "eagle-import:SOIC-16_ONS")
      (fields
        (field (name "MANUFACTURER_PART_NUMBER") "MC74HC165ADG")
        (field (name "COPYRIGHT") "Copyright (C) 2022 Ultra Librarian. All rights reserved.")
      )
      (libsource (lib "eagle-import") (part "MC74HC165ADGSOIC-16_ONS"))
    )
    (comp (ref "U4")
      (value "MC74HC165ADGSOIC-16_ONS")
      (footprint "eagle-import:SOIC-16_ONS")
      (fields
        (field (name "MANUFACTURER_PART_NUMBER") "MC74HC165ADG")
        (field (name "COPYRIGHT") "Copyright (C) 2022 Ultra Librarian. All rights reserved.")
      )
      (libsource (lib "eagle-import") (part "MC74HC165ADGSOIC-16_ONS"))
    )
    (comp (ref "U5")
      (value "MC74HC165ADGSOIC-16_ONS")
      (footprint "eagle-import:SOIC-16_ONS")
      (fields
        (field (name "MANUFACTURER_PART_NUMBER") "MC74HC165ADG")
        (field (name "COPYRIGHT") "Copyright (C) 2022 Ultra Librarian. All rights reserved.")
      )
      (libsource (lib "eagle-import") (part "MC74HC165ADGSOIC-16_ONS"))
    )
    (comp (ref "U6")
      (value "LMV324DR2GSOIC-14_NB_ONS-M")
      (footprint "eagle-import:SOIC-14_NB_ONS-M")
      (fields
        (field (name "MANUFACTURER_PART_NUMBER") "LMV324DR2G")
        (field (name "COPYRIGHT") "Copyright (C) 2022 Ultra Librarian. All rights reserved.")
      )
      (libsource (lib "eagle-import") (part "LMV324DR2GSOIC-14_NB_ONS-M"))
    )
  )
  (nets
    (net (code "1") (name "AGND") (class "Default")
      (node (ref "C1") (pin "-") (pinfunction "-_-") (pintype "passive"))
      (node (ref "C11") (pin "-") (pinfunction "-_-") (pintype "passive"))
      (node (ref "C13") (pin "-") (pinfunction "-_-") (pintype "passive"))
      (node (ref "C21") (pin "-") (pinfunction "-_-") (pintype "passive"))
      (node (ref "C23") (pin "-") (pinfunction "-_-") (pintype "passive"))
      (node (ref "C31") (pin "-") (pinfunction "-_-") (pintype "passive"))
      (node (ref "C33") (pin "-") (pinfunction "-_-") (pintype "passive"))
      (node (ref "C41") (pin "-") (pinfunction "-_-") (pintype "passive"))
      (node (ref "C43") (pin "-") (pinfunction "-_-") (pintype "passive"))
      (node (ref "SV10") (pin "10") (pinfunction "10_10") (pintype "passive"))
      (node (ref "SV10") (pin "12") (pinfunction "12_12") (pintype "passive"))
      (node (ref "SV10") (pin "14") (pinfunction "14_14") (pintype "passive"))
      (node (ref "SV10") (pin "16") (pinfunction "16_16") (pintype "passive"))
      (node (ref "SV10") (pin "2") (pinfunction "2_2") (pintype "passive"))
      (node (ref "SV10") (pin "4") (pinfunction "4_4") (pintype "passive"))
      (node (ref "SV10") (pin "6") (pinfunction "6_6") (pintype "passive"))
      (node (ref "SV10") (pin "8") (pinfunction "8_8") (pintype "passive"))
      (node (ref "SV11") (pin "10") (pinfunction "10_10") (pintype "passive"))
      (node (ref "SV11") (pin "12") (pinfunction "12_12") (pintype "passive"))
      (node (ref "SV11") (pin "14") (pinfunction "14_14") (pintype "passive"))
      (node (ref "SV11") (pin "16") (pinfunction "16_16") (pintype "passive"))
      (node (ref "SV11") (pin "2") (pinfunction "2_2") (pintype "passive"))
      (node (ref "SV11") (pin "4") (pinfunction "4_4") (pintype "passive"))
      (node (ref "SV11") (pin "6") (pinfunction "6_6") (pintype "passive"))
      (node (ref "SV11") (pin "8") (pinfunction "8_8") (pintype "passive"))
      (node (ref "SV7") (pin "10") (pinfunction "10_10") (pintype "passive"))
      (node (ref "SV7") (pin "12") (pinfunction "12_12") (pintype "passive"))
      (node (ref "SV7") (pin "14") (pinfunction "14_14") (pintype "passive"))
      (node (ref "SV7") (pin "16") (pinfunction "16_16") (pintype "passive"))
      (node (ref "SV7") (pin "2") (pinfunction "2_2") (pintype "passive"))
      (node (ref "SV7") (pin "4") (pinfunction "4_4") (pintype "passive"))
      (node (ref "SV7") (pin "6") (pinfunction "6_6") (pintype "passive"))
      (node (ref "SV7") (pin "8") (pinfunction "8_8") (pintype "passive"))
      (node (ref "SV8") (pin "10") (pinfunction "10_10") (pintype "passive"))
      (node (ref "SV8") (pin "12") (pinfunction "12_12") (pintype "passive"))
      (node (ref "SV8") (pin "14") (pinfunction "14_14") (pintype "passive"))
      (node (ref "SV8") (pin "16") (pinfunction "16_16") (pintype "passive"))
      (node (ref "SV8") (pin "2") (pinfunction "2_2") (pintype "passive"))
      (node (ref "SV8") (pin "4") (pinfunction "4_4") (pintype "passive"))
      (node (ref "SV8") (pin "6") (pinfunction "6_6") (pintype "passive"))
      (node (ref "SV8") (pin "8") (pinfunction "8_8") (pintype "passive"))
      (node (ref "SV9") (pin "10") (pinfunction "10_10") (pintype "passive"))
      (node (ref "SV9") (pin "12") (pinfunction "12_12") (pintype "passive"))
      (node (ref "SV9") (pin "14") (pinfunction "14_14") (pintype "passive"))
      (node (ref "SV9") (pin "16") (pinfunction "16_16") (pintype "passive"))
      (node (ref "SV9") (pin "2") (pinfunction "2_2") (pintype "passive"))
      (node (ref "SV9") (pin "4") (pinfunction "4_4") (pintype "passive"))
      (node (ref "SV9") (pin "6") (pinfunction "6_6") (pintype "passive"))
      (node (ref "SV9") (pin "8") (pinfunction "8_8") (pintype "passive"))
      (node (ref "U$1") (pin "GND@1") (pinfunction "GND_GND@1") (pintype "bidirectional"))
      (node (ref "U$1") (pin "GND@2") (pinfunction "GND_GND@2") (pintype "bidirectional"))
      (node (ref "U$1") (pin "GND@3") (pinfunction "GND_GND@3") (pintype "bidirectional"))
      (node (ref "U1") (pin "15") (pinfunction "CLOCKINHIBIT_15") (pintype "input"))
      (node (ref "U1") (pin "8") (pinfunction "GND_8") (pintype "power_in"))
      (node (ref "U2") (pin "15") (pinfunction "CLOCKINHIBIT_15") (pintype "input"))
      (node (ref "U2") (pin "8") (pinfunction "GND_8") (pintype "power_in"))
      (node (ref "U3") (pin "15") (pinfunction "CLOCKINHIBIT_15") (pintype "input"))
      (node (ref "U3") (pin "8") (pinfunction "GND_8") (pintype "power_in"))
      (node (ref "U4") (pin "15") (pinfunction "CLOCKINHIBIT_15") (pintype "input"))
      (node (ref "U4") (pin "8") (pinfunction "GND_8") (pintype "power_in"))
      (node (ref "U5") (pin "15") (pinfunction "CLOCKINHIBIT_15") (pintype "input"))
      (node (ref "U5") (pin "8") (pinfunction "GND_8") (pintype "power_in"))
      (node (ref "U6") (pin "11") (pinfunction "V-_11") (pintype "power_in"))
    )
    (net (code "2") (name "DGND") (class "Default")
      (node (ref "SV1") (pin "3") (pinfunction "3_3") (pintype "passive"))
      (node (ref "SV2") (pin "3") (pinfunction "3_3") (pintype "passive"))
      (node (ref "SV3") (pin "3") (pinfunction "3_3") (pintype "passive"))
      (node (ref "SV4") (pin "3") (pinfunction "3_3") (pintype "passive"))
    )
    (net (code "3") (name "Net-(C11-Pad+)") (class "Default")
      (node (ref "C11") (pin "+") (pinfunction "+_+") (pintype "passive"))
      (node (ref "R111") (pin "1") (pinfunction "1_1") (pintype "passive"))
      (node (ref "R112") (pin "2") (pinfunction "2_2") (pintype "passive"))
    )
    (net (code "4") (name "Net-(C12-Pad-)") (class "Default")
      (node (ref "C12") (pin "-") (pinfunction "-_-") (pintype "passive"))
      (node (ref "R112") (pin "1") (pinfunction "1_1") (pintype "passive"))
      (node (ref "R113") (pin "2") (pinfunction "2_2") (pintype "passive"))
    )
    (net (code "5") (name "Net-(C21-Pad+)") (class "Default")
      (node (ref "C21") (pin "+") (pinfunction "+_+") (pintype "passive"))
      (node (ref "R211") (pin "1") (pinfunction "1_1") (pintype "passive"))
      (node (ref "R212") (pin "2") (pinfunction "2_2") (pintype "passive"))
    )
    (net (code "6") (name "Net-(C22-Pad-)") (class "Default")
      (node (ref "C22") (pin "-") (pinfunction "-_-") (pintype "passive"))
      (node (ref "R212") (pin "1") (pinfunction "1_1") (pintype "passive"))
      (node (ref "R213") (pin "2") (pinfunction "2_2") (pintype "passive"))
    )
    (net (code "7") (name "Net-(C31-Pad+)") (class "Default")
      (node (ref "C31") (pin "+") (pinfunction "+_+") (pintype "passive"))
      (node (ref "R311") (pin "2") (pinfunction "2_2") (pintype "passive"))
      (node (ref "R312") (pin "1") (pinfunction "1_1") (pintype "passive"))
    )
    (net (code "8") (name "Net-(C32-Pad-)") (class "Default")
      (node (ref "C32") (pin "-") (pinfunction "-_-") (pintype "passive"))
      (node (ref "R312") (pin "2") (pinfunction "2_2") (pintype "passive"))
      (node (ref "R313") (pin "1") (pinfunction "1_1") (pintype "passive"))
    )
    (net (code "9") (name "Net-(C41-Pad+)") (class "Default")
      (node (ref "C41") (pin "+") (pinfunction "+_+") (pintype "passive"))
      (node (ref "R411") (pin "2") (pinfunction "2_2") (pintype "passive"))
      (node (ref "R412") (pin "1") (pinfunction "1_1") (pintype "passive"))
    )
    (net (code "10") (name "Net-(C42-Pad-)") (class "Default")
      (node (ref "C42") (pin "-") (pinfunction "-_-") (pintype "passive"))
      (node (ref "R412") (pin "2") (pinfunction "2_2") (pintype "passive"))
      (node (ref "R413") (pin "1") (pinfunction "1_1") (pintype "passive"))
    )
    (net (code "11") (name "Net-(R111-Pad2)") (class "Default")
      (node (ref "R111") (pin "2") (pinfunction "2_2") (pintype "passive"))
      (node (ref "SJ1") (pin "2") (pinfunction "2_2") (pintype "passive"))
      (node (ref "SV1") (pin "2") (pinfunction "2_2") (pintype "passive"))
    )
    (net (code "12") (name "Net-(R211-Pad2)") (class "Default")
      (node (ref "R211") (pin "2") (pinfunction "2_2") (pintype "passive"))
      (node (ref "SJ2") (pin "2") (pinfunction "2_2") (pintype "passive"))
      (node (ref "SV2") (pin "2") (pinfunction "2_2") (pintype "passive"))
    )
    (net (code "13") (name "Net-(R311-Pad1)") (class "Default")
      (node (ref "R311") (pin "1") (pinfunction "1_1") (pintype "passive"))
      (node (ref "SJ3") (pin "2") (pinfunction "2_2") (pintype "passive"))
      (node (ref "SV3") (pin "2") (pinfunction "2_2") (pintype "passive"))
    )
    (net (code "14") (name "Net-(R411-Pad1)") (class "Default")
      (node (ref "R411") (pin "1") (pinfunction "1_1") (pintype "passive"))
      (node (ref "SJ4") (pin "2") (pinfunction "2_2") (pintype "passive"))
      (node (ref "SV4") (pin "2") (pinfunction "2_2") (pintype "passive"))
    )
    (net (code "15") (name "Net-(SV5-Pad1)") (class "Default")
      (node (ref "SV5") (pin "1") (pinfunction "1_1") (pintype "passive"))
      (node (ref "U$1") (pin "PB_0") (pinfunction "PB_0_PB_0") (pintype "bidirectional"))
    )
    (net (code "16") (name "Net-(SV5-Pad2)") (class "Default")
      (node (ref "SV5") (pin "2") (pinfunction "2_2") (pintype "passive"))
      (node (ref "U$1") (pin "PB_1") (pinfunction "PB_1_PB_1") (pintype "bidirectional"))
    )
    (net (code "17") (name "Net-(SV5-Pad3)") (class "Default")
      (node (ref "SV5") (pin "3") (pinfunction "3_3") (pintype "passive"))
      (node (ref "U$1") (pin "PB_3") (pinfunction "PB_3_PB_3") (pintype "bidirectional"))
    )
    (net (code "18") (name "Net-(SV5-Pad4)") (class "Default")
      (node (ref "SV5") (pin "4") (pinfunction "4_4") (pintype "passive"))
      (node (ref "U$1") (pin "PB_4") (pinfunction "PB_4_PB_4") (pintype "bidirectional"))
    )
    (net (code "19") (name "Net-(SV5-Pad5)") (class "Default")
      (node (ref "SV5") (pin "5") (pinfunction "5_5") (pintype "passive"))
      (node (ref "U$1") (pin "PB_5") (pinfunction "PB_5_PB_5") (pintype "bidirectional"))
    )
    (net (code "20") (name "Net-(SV5-Pad6)") (class "Default")
      (node (ref "SV5") (pin "6") (pinfunction "6_6") (pintype "passive"))
      (node (ref "U$1") (pin "PB_6") (pinfunction "PB_6_PB_6") (pintype "bidirectional"))
    )
    (net (code "21") (name "Net-(SV5-Pad7)") (class "Default")
      (node (ref "SV5") (pin "7") (pinfunction "7_7") (pintype "passive"))
      (node (ref "U$1") (pin "PB_7") (pinfunction "PB_7_PB_7") (pintype "bidirectional"))
    )
    (net (code "22") (name "Net-(SV5-Pad8)") (class "Default")
      (node (ref "SV5") (pin "8") (pinfunction "8_8") (pintype "passive"))
      (node (ref "U$1") (pin "PB_8") (pinfunction "PB_8_PB_8") (pintype "bidirectional"))
    )
    (net (code "23") (name "Net-(SV5-Pad9)") (class "Default")
      (node (ref "SV5") (pin "9") (pinfunction "9_9") (pintype "passive"))
      (node (ref "U$1") (pin "PB_9") (pinfunction "PB_9_PB_9") (pintype "bidirectional"))
    )
    (net (code "24") (name "Net-(SV5-Pad10)") (class "Default")
      (node (ref "SV5") (pin "10") (pinfunction "10_10") (pintype "passive"))
      (node (ref "U$1") (pin "PB_10") (pinfunction "PB_10_PB_10") (pintype "bidirectional"))
    )
    (net (code "25") (name "Net-(SV5-Pad11)") (class "Default")
      (node (ref "SV5") (pin "11") (pinfunction "11_11") (pintype "passive"))
      (node (ref "U$1") (pin "PB_11") (pinfunction "PB_11_PB_11") (pintype "bidirectional"))
    )
    (net (code "26") (name "Net-(SV5-Pad12)") (class "Default")
      (node (ref "SV5") (pin "12") (pinfunction "12_12") (pintype "passive"))
      (node (ref "U$1") (pin "PB_12") (pinfunction "PB_12_PB_12") (pintype "bidirectional"))
    )
    (net (code "27") (name "Net-(SV5-Pad13)") (class "Default")
      (node (ref "SV5") (pin "13") (pinfunction "13_13") (pintype "passive"))
      (node (ref "U$1") (pin "PB_13") (pinfunction "PB_13_PB_13") (pintype "bidirectional"))
    )
    (net (code "28") (name "Net-(SV6-Pad1)") (class "Default")
      (node (ref "SV6") (pin "1") (pinfunction "1_1") (pintype "passive"))
      (node (ref "U$1") (pin "PB_14") (pinfunction "PB_14_PB_14") (pintype "bidirectional"))
    )
    (net (code "29") (name "Net-(SV6-Pad2)") (class "Default")
      (node (ref "SV6") (pin "2") (pinfunction "2_2") (pintype "passive"))
      (node (ref "U$1") (pin "PB_15") (pinfunction "PB_15_PB_15") (pintype "bidirectional"))
    )
    (net (code "30") (name "Net-(SV6-Pad3)") (class "Default")
      (node (ref "SV6") (pin "3") (pinfunction "3_3") (pintype "passive"))
      (node (ref "U$1") (pin "PC_13") (pinfunction "PC_13_PC_13") (pintype "bidirectional"))
    )
    (net (code "31") (name "Net-(SV6-Pad4)") (class "Default")
      (node (ref "SV6") (pin "4") (pinfunction "4_4") (pintype "passive"))
      (node (ref "U$1") (pin "PC_14") (pinfunction "PC_14_PC_14") (pintype "bidirectional"))
    )
    (net (code "32") (name "Net-(SV6-Pad5)") (class "Default")
      (node (ref "SV6") (pin "5") (pinfunction "5_5") (pintype "passive"))
      (node (ref "U$1") (pin "PC_15") (pinfunction "PC_15_PC_15") (pintype "bidirectional"))
    )
    (net (code "33") (name "Net-(SV6-Pad6)") (class "Default")
      (node (ref "SV6") (pin "6") (pinfunction "6_6") (pintype "passive"))
      (node (ref "U$1") (pin "5V") (pinfunction "5V_5V") (pintype "bidirectional"))
    )
    (net (code "34") (name "Net-(SV6-Pad7)") (class "Default")
      (node (ref "SV6") (pin "7") (pinfunction "7_7") (pintype "passive"))
      (node (ref "U$1") (pin "PA_2") (pinfunction "PA_2_PA_2") (pintype "bidirectional"))
    )
    (net (code "35") (name "Net-(SV6-Pad8)") (class "Default")
      (node (ref "SV6") (pin "8") (pinfunction "8_8") (pintype "passive"))
      (node (ref "U$1") (pin "PA_15") (pinfunction "PA_15_PA_15") (pintype "bidirectional"))
    )
    (net (code "36") (name "Net-(SV6-Pad9)") (class "Default")
      (node (ref "SV6") (pin "9") (pinfunction "9_9") (pintype "passive"))
      (node (ref "U$1") (pin "PA_12") (pinfunction "PA_12_PA_12") (pintype "bidirectional"))
    )
    (net (code "37") (name "Net-(SV6-Pad10)") (class "Default")
      (node (ref "SV6") (pin "10") (pinfunction "10_10") (pintype "passive"))
      (node (ref "U$1") (pin "PA_11") (pinfunction "PA_11_PA_11") (pintype "bidirectional"))
    )
    (net (code "38") (name "Net-(SV6-Pad11)") (class "Default")
      (node (ref "SV6") (pin "11") (pinfunction "11_11") (pintype "passive"))
      (node (ref "U$1") (pin "PA_10") (pinfunction "PA_10_PA_10") (pintype "bidirectional"))
    )
    (net (code "39") (name "Net-(SV6-Pad12)") (class "Default")
      (node (ref "SV6") (pin "12") (pinfunction "12_12") (pintype "passive"))
      (node (ref "U$1") (pin "PA_9") (pinfunction "PA_9_PA_9") (pintype "bidirectional"))
    )
    (net (code "40") (name "Net-(SV6-Pad13)") (class "Default")
      (node (ref "SV6") (pin "13") (pinfunction "13_13") (pintype "passive"))
      (node (ref "U$1") (pin "PA_8") (pinfunction "PA_8_PA_8") (pintype "bidirectional"))
    )
    (net (code "41") (name "Net-(U1-A)") (class "Default")
      (node (ref "R1") (pin "2") (pinfunction "2_2") (pintype "passive"))
      (node (ref "SV7") (pin "15") (pinfunction "15_15") (pintype "passive"))
      (node (ref "U1") (pin "11") (pinfunction "A_11") (pintype "input"))
    )
    (net (code "42") (name "Net-(U1-B)") (class "Default")
      (node (ref "R2") (pin "2") (pinfunction "2_2") (pintype "passive"))
      (node (ref "SV7") (pin "13") (pinfunction "13_13") (pintype "passive"))
      (node (ref "U1") (pin "12") (pinfunction "B_12") (pintype "input"))
    )
    (net (code "43") (name "Net-(U1-C)") (class "Default")
      (node (ref "R3") (pin "2") (pinfunction "2_2") (pintype "passive"))
      (node (ref "SV7") (pin "11") (pinfunction "11_11") (pintype "passive"))
      (node (ref "U1") (pin "13") (pinfunction "C_13") (pintype "input"))
    )
    (net (code "44") (name "Net-(U1-CLOCK)") (class "Default")
      (node (ref "U$1") (pin "PA_3") (pinfunction "PA_3_PA_3") (pintype "bidirectional"))
      (node (ref "U1") (pin "2") (pinfunction "CLOCK_2") (pintype "input"))
      (node (ref "U2") (pin "2") (pinfunction "CLOCK_2") (pintype "input"))
      (node (ref "U3") (pin "2") (pinfunction "CLOCK_2") (pintype "input"))
      (node (ref "U4") (pin "2") (pinfunction "CLOCK_2") (pintype "input"))
      (node (ref "U5") (pin "2") (pinfunction "CLOCK_2") (pintype "input"))
    )
    (net (code "45") (name "Net-(U1-D)") (class "Default")
      (node (ref "R4") (pin "2") (pinfunction "2_2") (pintype "passive"))
      (node (ref "SV7") (pin "9") (pinfunction "9_9") (pintype "passive"))
      (node (ref "U1") (pin "14") (pinfunction "D_14") (pintype "input"))
    )
    (net (code "46") (name "Net-(U1-E)") (class "Default")
      (node (ref "R5") (pin "2") (pinfunction "2_2") (pintype "passive"))
      (node (ref "SV7") (pin "7") (pinfunction "7_7") (pintype "passive"))
      (node (ref "U1") (pin "3") (pinfunction "E_3") (pintype "input"))
    )
    (net (code "47") (name "Net-(U1-F)") (class "Default")
      (node (ref "R6") (pin "2") (pinfunction "2_2") (pintype "passive"))
      (node (ref "SV7") (pin "5") (pinfunction "5_5") (pintype "passive"))
      (node (ref "U1") (pin "4") (pinfunction "F_4") (pintype "input"))
    )
    (net (code "48") (name "Net-(U1-G)") (class "Default")
      (node (ref "R7") (pin "2") (pinfunction "2_2") (pintype "passive"))
      (node (ref "SV7") (pin "3") (pinfunction "3_3") (pintype "passive"))
      (node (ref "U1") (pin "5") (pinfunction "G_5") (pintype "input"))
    )
    (net (code "49") (name "Net-(U1-H)") (class "Default")
      (node (ref "R8") (pin "2") (pinfunction "2_2") (pintype "passive"))
      (node (ref "SV7") (pin "1") (pinfunction "1_1") (pintype "passive"))
      (node (ref "U1") (pin "6") (pinfunction "H_6") (pintype "input"))
    )
    (net (code "50") (name "Net-(U1-QH)") (class "Default")
      (node (ref "U1") (pin "9") (pinfunction "QH_9") (pintype "output"))
      (node (ref "U2") (pin "10") (pinfunction "SA_10") (pintype "input"))
    )
    (net (code "51") (name "Net-(U1-SERIALSHIFT{slash}~{PARALLELLOAD})") (class "Default")
      (node (ref "U$1") (pin "PA_5") (pinfunction "PA_5_PA_5") (pintype "bidirectional"))
      (node (ref "U1") (pin "1") (pinfunction "SERIALSHIFT/~{PARALLELLOAD}_1") (pintype "input"))
      (node (ref "U2") (pin "1") (pinfunction "SERIALSHIFT/~{PARALLELLOAD}_1") (pintype "input"))
      (node (ref "U3") (pin "1") (pinfunction "SERIALSHIFT/~{PARALLELLOAD}_1") (pintype "input"))
      (node (ref "U4") (pin "1") (pinfunction "SERIALSHIFT/~{PARALLELLOAD}_1") (pintype "input"))
      (node (ref "U5") (pin "1") (pinfunction "SERIALSHIFT/~{PARALLELLOAD}_1") (pintype "input"))
    )
    (net (code "52") (name "Net-(U2-A)") (class "Default")
      (node (ref "R9") (pin "2") (pinfunction "2_2") (pintype "passive"))
      (node (ref "SV8") (pin "15") (pinfunction "15_15") (pintype "passive"))
      (node (ref "U2") (pin "11") (pinfunction "A_11") (pintype "input"))
    )
    (net (code "53") (name "Net-(U2-B)") (class "Default")
      (node (ref "R10") (pin "2") (pinfunction "2_2") (pintype "passive"))
      (node (ref "SV8") (pin "13") (pinfunction "13_13") (pintype "passive"))
      (node (ref "U2") (pin "12") (pinfunction "B_12") (pintype "input"))
    )
    (net (code "54") (name "Net-(U2-C)") (class "Default")
      (node (ref "R11") (pin "2") (pinfunction "2_2") (pintype "passive"))
      (node (ref "SV8") (pin "11") (pinfunction "11_11") (pintype "passive"))
      (node (ref "U2") (pin "13") (pinfunction "C_13") (pintype "input"))
    )
    (net (code "55") (name "Net-(U2-D)") (class "Default")
      (node (ref "R12") (pin "2") (pinfunction "2_2") (pintype "passive"))
      (node (ref "SV8") (pin "9") (pinfunction "9_9") (pintype "passive"))
      (node (ref "U2") (pin "14") (pinfunction "D_14") (pintype "input"))
    )
    (net (code "56") (name "Net-(U2-E)") (class "Default")
      (node (ref "R13") (pin "2") (pinfunction "2_2") (pintype "passive"))
      (node (ref "SV8") (pin "7") (pinfunction "7_7") (pintype "passive"))
      (node (ref "U2") (pin "3") (pinfunction "E_3") (pintype "input"))
    )
    (net (code "57") (name "Net-(U2-F)") (class "Default")
      (node (ref "R14") (pin "2") (pinfunction "2_2") (pintype "passive"))
      (node (ref "SV8") (pin "5") (pinfunction "5_5") (pintype "passive"))
      (node (ref "U2") (pin "4") (pinfunction "F_4") (pintype "input"))
    )
    (net (code "58") (name "Net-(U2-G)") (class "Default")
      (node (ref "R15") (pin "2") (pinfunction "2_2") (pintype "passive"))
      (node (ref "SV8") (pin "3") (pinfunction "3_3") (pintype "passive"))
      (node (ref "U2") (pin "5") (pinfunction "G_5") (pintype "input"))
    )
    (net (code "59") (name "Net-(U2-H)") (class "Default")
      (node (ref "R16") (pin "2") (pinfunction "2_2") (pintype "passive"))
      (node (ref "SV8") (pin "1") (pinfunction "1_1") (pintype "passive"))
      (node (ref "U2") (pin "6") (pinfunction "H_6") (pintype "input"))
    )
    (net (code "60") (name "Net-(U2-QH)") (class "Default")
      (node (ref "U2") (pin "9") (pinfunction "QH_9") (pintype "output"))
      (node (ref "U3") (pin "10") (pinfunction "SA_10") (pintype "input"))
    )
    (net (code "61") (name "Net-(U3-A)") (class "Default")
      (node (ref "R17") (pin "2") (pinfunction "2_2") (pintype "passive"))
      (node (ref "SV9") (pin "15") (pinfunction "15_15") (pintype "passive"))
      (node (ref "U3") (pin "11") (pinfunction "A_11") (pintype "input"))
    )
    (net (code "62") (name "Net-(U3-B)") (class "Default")
      (node (ref "R18") (pin "2") (pinfunction "2_2") (pintype "passive"))
      (node (ref "SV9") (pin "13") (pinfunction "13_13") (pintype "passive"))
      (node (ref "U3") (pin "12") (pinfunction "B_12") (pintype "input"))
    )
    (net (code "63") (name "Net-(U3-C)") (class "Default")
      (node (ref "R19") (pin "2") (pinfunction "2_2") (pintype "passive"))
      (node (ref "SV9") (pin "11") (pinfunction "11_11") (pintype "passive"))
      (node (ref "U3") (pin "13") (pinfunction "C_13") (pintype "input"))
    )
    (net (code "64") (name "Net-(U3-D)") (class "Default")
      (node (ref "R20") (pin "2") (pinfunction "2_2") (pintype "passive"))
      (node (ref "SV9") (pin "9") (pinfunction "9_9") (pintype "passive"))
      (node (ref "U3") (pin "14") (pinfunction "D_14") (pintype "input"))
    )
    (net (code "65") (name "Net-(U3-E)") (class "Default")
      (node (ref "R21") (pin "2") (pinfunction "2_2") (pintype "passive"))
      (node (ref "SV9") (pin "7") (pinfunction "7_7") (pintype "passive"))
      (node (ref "U3") (pin "3") (pinfunction "E_3") (pintype "input"))
    )
    (net (code "66") (name "Net-(U3-F)") (class "Default")
      (node (ref "R22") (pin "2") (pinfunction "2_2") (pintype "passive"))
      (node (ref "SV9") (pin "5") (pinfunction "5_5") (pintype "passive"))
      (node (ref "U3") (pin "4") (pinfunction "F_4") (pintype "input"))
    )
    (net (code "67") (name "Net-(U3-G)") (class "Default")
      (node (ref "R23") (pin "2") (pinfunction "2_2") (pintype "passive"))
      (node (ref "SV9") (pin "3") (pinfunction "3_3") (pintype "passive"))
      (node (ref "U3") (pin "5") (pinfunction "G_5") (pintype "input"))
    )
    (net (code "68") (name "Net-(U3-H)") (class "Default")
      (node (ref "R24") (pin "2") (pinfunction "2_2") (pintype "passive"))
      (node (ref "SV9") (pin "1") (pinfunction "1_1") (pintype "passive"))
      (node (ref "U3") (pin "6") (pinfunction "H_6") (pintype "input"))
    )
    (net (code "69") (name "Net-(U3-QH)") (class "Default")
      (node (ref "U3") (pin "9") (pinfunction "QH_9") (pintype "output"))
      (node (ref "U4") (pin "10") (pinfunction "SA_10") (pintype "input"))
    )
    (net (code "70") (name "Net-(U4-A)") (class "Default")
      (node (ref "R25") (pin "2") (pinfunction "2_2") (pintype "passive"))
      (node (ref "SV10") (pin "15") (pinfunction "15_15") (pintype "passive"))
      (node (ref "U4") (pin "11") (pinfunction "A_11") (pintype "input"))
    )
    (net (code "71") (name "Net-(U4-B)") (class "Default")
      (node (ref "R26") (pin "2") (pinfunction "2_2") (pintype "passive"))
      (node (ref "SV10") (pin "13") (pinfunction "13_13") (pintype "passive"))
      (node (ref "U4") (pin "12") (pinfunction "B_12") (pintype "input"))
    )
    (net (code "72") (name "Net-(U4-C)") (class "Default")
      (node (ref "R27") (pin "2") (pinfunction "2_2") (pintype "passive"))
      (node (ref "SV10") (pin "11") (pinfunction "11_11") (pintype "passive"))
      (node (ref "U4") (pin "13") (pinfunction "C_13") (pintype "input"))
    )
    (net (code "73") (name "Net-(U4-D)") (class "Default")
      (node (ref "R28") (pin "2") (pinfunction "2_2") (pintype "passive"))
      (node (ref "SV10") (pin "9") (pinfunction "9_9") (pintype "passive"))
      (node (ref "U4") (pin "14") (pinfunction "D_14") (pintype "input"))
    )
    (net (code "74") (name "Net-(U4-E)") (class "Default")
      (node (ref "R29") (pin "2") (pinfunction "2_2") (pintype "passive"))
      (node (ref "SV10") (pin "7") (pinfunction "7_7") (pintype "passive"))
      (node (ref "U4") (pin "3") (pinfunction "E_3") (pintype "input"))
    )
    (net (code "75") (name "Net-(U4-F)") (class "Default")
      (node (ref "R30") (pin "2") (pinfunction "2_2") (pintype "passive"))
      (node (ref "SV10") (pin "5") (pinfunction "5_5") (pintype "passive"))
      (node (ref "U4") (pin "4") (pinfunction "F_4") (pintype "input"))
    )
    (net (code "76") (name "Net-(U4-G)") (class "Default")
      (node (ref "R31") (pin "2") (pinfunction "2_2") (pintype "passive"))
      (node (ref "SV10") (pin "3") (pinfunction "3_3") (pintype "passive"))
      (node (ref "U4") (pin "5") (pinfunction "G_5") (pintype "input"))
    )
    (net (code "77") (name "Net-(U4-H)") (class "Default")
      (node (ref "R32") (pin "2") (pinfunction "2_2") (pintype "passive"))
      (node (ref "SV10") (pin "1") (pinfunction "1_1") (pintype "passive"))
      (node (ref "U4") (pin "6") (pinfunction "H_6") (pintype "input"))
    )
    (net (code "78") (name "Net-(U4-QH)") (class "Default")
      (node (ref "U4") (pin "9") (pinfunction "QH_9") (pintype "output"))
      (node (ref "U5") (pin "10") (pinfunction "SA_10") (pintype "input"))
    )
    (net (code "79") (name "Net-(U5-A)") (class "Default")
      (node (ref "R33") (pin "2") (pinfunction "2_2") (pintype "passive"))
      (node (ref "SV11") (pin "15") (pinfunction "15_15") (pintype "passive"))
      (node (ref "U5") (pin "11") (pinfunction "A_11") (pintype "input"))
    )
    (net (code "80") (name "Net-(U5-B)") (class "Default")
      (node (ref "R34") (pin "2") (pinfunction "2_2") (pintype "passive"))
      (node (ref "SV11") (pin "13") (pinfunction "13_13") (pintype "passive"))
      (node (ref "U5") (pin "12") (pinfunction "B_12") (pintype "input"))
    )
    (net (code "81") (name "Net-(U5-C)") (class "Default")
      (node (ref "R35") (pin "2") (pinfunction "2_2") (pintype "passive"))
      (node (ref "SV11") (pin "11") (pinfunction "11_11") (pintype "passive"))
      (node (ref "U5") (pin "13") (pinfunction "C_13") (pintype "input"))
    )
    (net (code "82") (name "Net-(U5-D)") (class "Default")
      (node (ref "R36") (pin "2") (pinfunction "2_2") (pintype "passive"))
      (node (ref "SV11") (pin "9") (pinfunction "9_9") (pintype "passive"))
      (node (ref "U5") (pin "14") (pinfunction "D_14") (pintype "input"))
    )
    (net (code "83") (name "Net-(U5-E)") (class "Default")
      (node (ref "R37") (pin "2") (pinfunction "2_2") (pintype "passive"))
      (node (ref "SV11") (pin "7") (pinfunction "7_7") (pintype "passive"))
      (node (ref "U5") (pin "3") (pinfunction "E_3") (pintype "input"))
    )
    (net (code "84") (name "Net-(U5-F)") (class "Default")
      (node (ref "R38") (pin "2") (pinfunction "2_2") (pintype "passive"))
      (node (ref "SV11") (pin "5") (pinfunction "5_5") (pintype "passive"))
      (node (ref "U5") (pin "4") (pinfunction "F_4") (pintype "input"))
    )
    (net (code "85") (name "Net-(U5-G)") (class "Default")
      (node (ref "R39") (pin "2") (pinfunction "2_2") (pintype "passive"))
      (node (ref "SV11") (pin "3") (pinfunction "3_3") (pintype "passive"))
      (node (ref "U5") (pin "5") (pinfunction "G_5") (pintype "input"))
    )
    (net (code "86") (name "Net-(U5-H)") (class "Default")
      (node (ref "R40") (pin "2") (pinfunction "2_2") (pintype "passive"))
      (node (ref "SV11") (pin "1") (pinfunction "1_1") (pintype "passive"))
      (node (ref "U5") (pin "6") (pinfunction "H_6") (pintype "input"))
    )
    (net (code "87") (name "Net-(U5-QH)") (class "Default")
      (node (ref "U$1") (pin "PA_4") (pinfunction "PA_4_PA_4") (pintype "bidirectional"))
      (node (ref "U5") (pin "9") (pinfunction "QH_9") (pintype "output"))
    )
    (net (code "88") (name "Net-(U6-INA+)") (class "Default")
      (node (ref "C13") (pin "+") (pinfunction "+_+") (pintype "passive"))
      (node (ref "R113") (pin "1") (pinfunction "1_1") (pintype "passive"))
      (node (ref "U6") (pin "3") (pinfunction "INA+_3") (pintype "input"))
    )
    (net (code "89") (name "Net-(U6-INA-)") (class "Default")
      (node (ref "C12") (pin "+") (pinfunction "+_+") (pintype "passive"))
      (node (ref "SJ1") (pin "1") (pinfunction "1_1") (pintype "passive"))
      (node (ref "U$1") (pin "PA_7") (pinfunction "PA_7_PA_7") (pintype "bidirectional"))
      (node (ref "U6") (pin "1") (pinfunction "OUTA_1") (pintype "output"))
      (node (ref "U6") (pin "2") (pinfunction "INA-_2") (pintype "input"))
    )
    (net (code "90") (name "Net-(U6-INB+)") (class "Default")
      (node (ref "C23") (pin "+") (pinfunction "+_+") (pintype "passive"))
      (node (ref "R213") (pin "1") (pinfunction "1_1") (pintype "passive"))
      (node (ref "U6") (pin "5") (pinfunction "INB+_5") (pintype "input"))
    )
    (net (code "91") (name "Net-(U6-INB-)") (class "Default")
      (node (ref "C22") (pin "+") (pinfunction "+_+") (pintype "passive"))
      (node (ref "SJ2") (pin "1") (pinfunction "1_1") (pintype "passive"))
      (node (ref "U$1") (pin "PA_6") (pinfunction "PA_6_PA_6") (pintype "bidirectional"))
      (node (ref "U6") (pin "6") (pinfunction "INB-_6") (pintype "input"))
      (node (ref "U6") (pin "7") (pinfunction "OUTB_7") (pintype "output"))
    )
    (net (code "92") (name "Net-(U6-INC+)") (class "Default")
      (node (ref "C43") (pin "+") (pinfunction "+_+") (pintype "passive"))
      (node (ref "R413") (pin "2") (pinfunction "2_2") (pintype "passive"))
      (node (ref "U6") (pin "10") (pinfunction "INC+_10") (pintype "input"))
    )
    (net (code "93") (name "Net-(U6-INC-)") (class "Default")
      (node (ref "C42") (pin "+") (pinfunction "+_+") (pintype "passive"))
      (node (ref "SJ4") (pin "1") (pinfunction "1_1") (pintype "passive"))
      (node (ref "U$1") (pin "PA_1") (pinfunction "PA_1_PA_1") (pintype "bidirectional"))
      (node (ref "U6") (pin "8") (pinfunction "OUTC_8") (pintype "output"))
      (node (ref "U6") (pin "9") (pinfunction "INC-_9") (pintype "input"))
    )
    (net (code "94") (name "Net-(U6-IND+)") (class "Default")
      (node (ref "C33") (pin "+") (pinfunction "+_+") (pintype "passive"))
      (node (ref "R313") (pin "2") (pinfunction "2_2") (pintype "passive"))
      (node (ref "U6") (pin "12") (pinfunction "IND+_12") (pintype "input"))
    )
    (net (code "95") (name "Net-(U6-IND-)") (class "Default")
      (node (ref "C32") (pin "+") (pinfunction "+_+") (pintype "passive"))
      (node (ref "SJ3") (pin "1") (pinfunction "1_1") (pintype "passive"))
      (node (ref "U$1") (pin "PA_0") (pinfunction "PA_0_PA_0") (pintype "bidirectional"))
      (node (ref "U6") (pin "13") (pinfunction "IND-_13") (pintype "input"))
      (node (ref "U6") (pin "14") (pinfunction "OUTD_14") (pintype "output"))
    )
    (net (code "96") (name "VCC") (class "Default")
      (node (ref "C1") (pin "+") (pinfunction "+_+") (pintype "passive"))
      (node (ref "R1") (pin "1") (pinfunction "1_1") (pintype "passive"))
      (node (ref "R10") (pin "1") (pinfunction "1_1") (pintype "passive"))
      (node (ref "R11") (pin "1") (pinfunction "1_1") (pintype "passive"))
      (node (ref "R12") (pin "1") (pinfunction "1_1") (pintype "passive"))
      (node (ref "R13") (pin "1") (pinfunction "1_1") (pintype "passive"))
      (node (ref "R14") (pin "1") (pinfunction "1_1") (pintype "passive"))
      (node (ref "R15") (pin "1") (pinfunction "1_1") (pintype "passive"))
      (node (ref "R16") (pin "1") (pinfunction "1_1") (pintype "passive"))
      (node (ref "R17") (pin "1") (pinfunction "1_1") (pintype "passive"))
      (node (ref "R18") (pin "1") (pinfunction "1_1") (pintype "passive"))
      (node (ref "R19") (pin "1") (pinfunction "1_1") (pintype "passive"))
      (node (ref "R2") (pin "1") (pinfunction "1_1") (pintype "passive"))
      (node (ref "R20") (pin "1") (pinfunction "1_1") (pintype "passive"))
      (node (ref "R21") (pin "1") (pinfunction "1_1") (pintype "passive"))
      (node (ref "R22") (pin "1") (pinfunction "1_1") (pintype "passive"))
      (node (ref "R23") (pin "1") (pinfunction "1_1") (pintype "passive"))
      (node (ref "R24") (pin "1") (pinfunction "1_1") (pintype "passive"))
      (node (ref "R25") (pin "1") (pinfunction "1_1") (pintype "passive"))
      (node (ref "R26") (pin "1") (pinfunction "1_1") (pintype "passive"))
      (node (ref "R27") (pin "1") (pinfunction "1_1") (pintype "passive"))
      (node (ref "R28") (pin "1") (pinfunction "1_1") (pintype "passive"))
      (node (ref "R29") (pin "1") (pinfunction "1_1") (pintype "passive"))
      (node (ref "R3") (pin "1") (pinfunction "1_1") (pintype "passive"))
      (node (ref "R30") (pin "1") (pinfunction "1_1") (pintype "passive"))
      (node (ref "R31") (pin "1") (pinfunction "1_1") (pintype "passive"))
      (node (ref "R32") (pin "1") (pinfunction "1_1") (pintype "passive"))
      (node (ref "R33") (pin "1") (pinfunction "1_1") (pintype "passive"))
      (node (ref "R34") (pin "1") (pinfunction "1_1") (pintype "passive"))
      (node (ref "R35") (pin "1") (pinfunction "1_1") (pintype "passive"))
      (node (ref "R36") (pin "1") (pinfunction "1_1") (pintype "passive"))
      (node (ref "R37") (pin "1") (pinfunction "1_1") (pintype "passive"))
      (node (ref "R38") (pin "1") (pinfunction "1_1") (pintype "passive"))
      (node (ref "R39") (pin "1") (pinfunction "1_1") (pintype "passive"))
      (node (ref "R4") (pin "1") (pinfunction "1_1") (pintype "passive"))
      (node (ref "R40") (pin "1") (pinfunction "1_1") (pintype "passive"))
      (node (ref "R5") (pin "1") (pinfunction "1_1") (pintype "passive"))
      (node (ref "R6") (pin "1") (pinfunction "1_1") (pintype "passive"))
      (node (ref "R7") (pin "1") (pinfunction "1_1") (pintype "passive"))
      (node (ref "R8") (pin "1") (pinfunction "1_1") (pintype "passive"))
      (node (ref "R9") (pin "1") (pinfunction "1_1") (pintype "passive"))
      (node (ref "SV1") (pin "1") (pinfunction "1_1") (pintype "passive"))
      (node (ref "SV2") (pin "1") (pinfunction "1_1") (pintype "passive"))
      (node (ref "SV3") (pin "1") (pinfunction "1_1") (pintype "passive"))
      (node (ref "SV4") (pin "1") (pinfunction "1_1") (pintype "passive"))
      (node (ref "U$1") (pin "3.3V@1") (pinfunction "3.3V_3.3V@1") (pintype "bidirectional"))
      (node (ref "U$1") (pin "3.3V@2") (pinfunction "3.3V_3.3V@2") (pintype "bidirectional"))
      (node (ref "U1") (pin "16") (pinfunction "VCC_16") (pintype "power_in"))
      (node (ref "U2") (pin "16") (pinfunction "VCC_16") (pintype "power_in"))
      (node (ref "U3") (pin "16") (pinfunction "VCC_16") (pintype "power_in"))
      (node (ref "U4") (pin "16") (pinfunction "VCC_16") (pintype "power_in"))
      (node (ref "U5") (pin "16") (pinfunction "VCC_16") (pintype "power_in"))
      (node (ref "U6") (pin "4") (pinfunction "V+_4") (pintype "power_in"))
    )
    (net (code "97") (name "unconnected-(U$1-PadRESET)") (class "Default")
      (node (ref "U$1") (pin "RESET") (pinfunction "RESET_RESET") (pintype "bidirectional"))
    )
    (net (code "98") (name "unconnected-(U$1-PadVB)") (class "Default")
      (node (ref "U$1") (pin "VB") (pinfunction "VB_VB") (pintype "bidirectional"))
    )
    (net (code "99") (name "unconnected-(U1-SA-Pad10)") (class "Default")
      (node (ref "U1") (pin "10") (pinfunction "SA_10") (pintype "input"))
    )
    (net (code "100") (name "unconnected-(U1-~{QH}-Pad7)") (class "Default")
      (node (ref "U1") (pin "7") (pinfunction "~{QH}_7") (pintype "output"))
    )
    (net (code "101") (name "unconnected-(U2-~{QH}-Pad7)") (class "Default")
      (node (ref "U2") (pin "7") (pinfunction "~{QH}_7") (pintype "output"))
    )
    (net (code "102") (name "unconnected-(U3-~{QH}-Pad7)") (class "Default")
      (node (ref "U3") (pin "7") (pinfunction "~{QH}_7") (pintype "output"))
    )
    (net (code "103") (name "unconnected-(U4-~{QH}-Pad7)") (class "Default")
      (node (ref "U4") (pin "7") (pinfunction "~{QH}_7") (pintype "output"))
    )
    (net (code "104") (name "unconnected-(U5-~{QH}-Pad7)") (class "Default")
      (node (ref "U5") (pin "7") (pinfunction "~{QH}_7") (pintype "output"))
    )
  )
)
